# tester.net
KiCad netlist of a schematic drawn in EAGLE
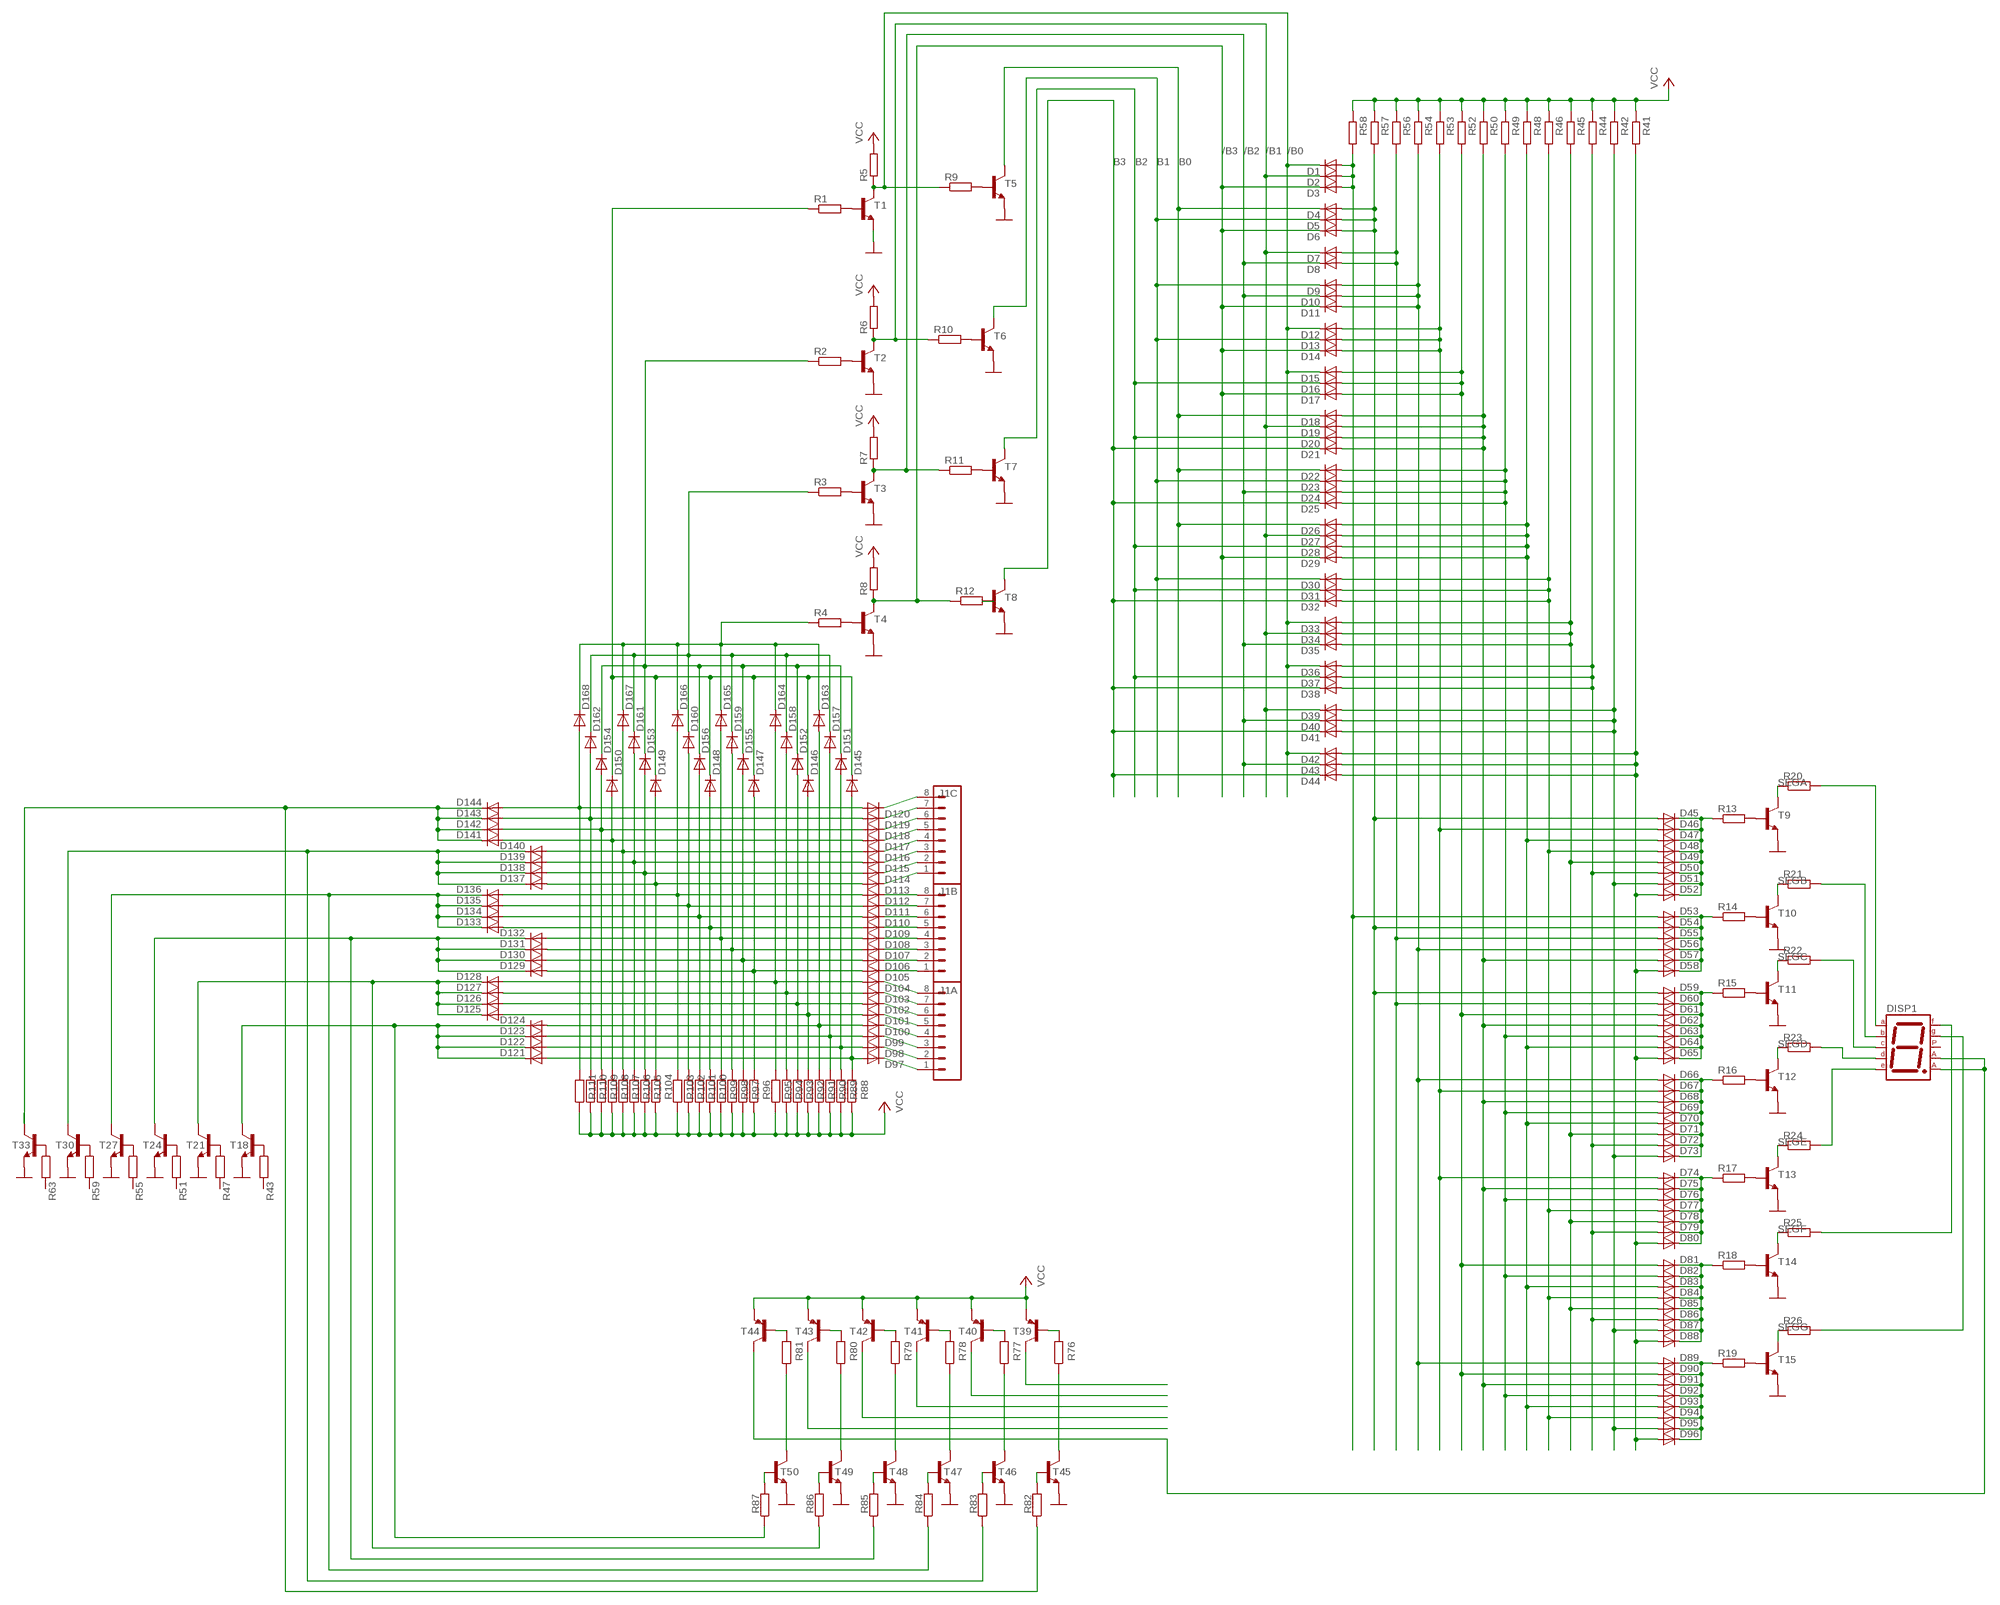
[diagram p0: schematic, sheet 1]

(export (version "E")
  (design (tool "Eeschema 10.0.6"))
  (components
    (comp (ref "D1")
      (value "SMALL_DIODEDO35-7")
      (footprint "eagle-import:DO35-7")
      (libsource (lib "eagle-import") (part "SMALL_DIODEDO35-7"))
    )
    (comp (ref "D2")
      (value "SMALL_DIODEDO35-7")
      (footprint "eagle-import:DO35-7")
      (libsource (lib "eagle-import") (part "SMALL_DIODEDO35-7"))
    )
    (comp (ref "D3")
      (value "SMALL_DIODEDO35-7")
      (footprint "eagle-import:DO35-7")
      (libsource (lib "eagle-import") (part "SMALL_DIODEDO35-7"))
    )
    (comp (ref "D4")
      (value "SMALL_DIODEDO35-7")
      (footprint "eagle-import:DO35-7")
      (libsource (lib "eagle-import") (part "SMALL_DIODEDO35-7"))
    )
    (comp (ref "D5")
      (value "SMALL_DIODEDO35-7")
      (footprint "eagle-import:DO35-7")
      (libsource (lib "eagle-import") (part "SMALL_DIODEDO35-7"))
    )
    (comp (ref "D6")
      (value "SMALL_DIODEDO35-7")
      (footprint "eagle-import:DO35-7")
      (libsource (lib "eagle-import") (part "SMALL_DIODEDO35-7"))
    )
    (comp (ref "D7")
      (value "SMALL_DIODEDO35-7")
      (footprint "eagle-import:DO35-7")
      (libsource (lib "eagle-import") (part "SMALL_DIODEDO35-7"))
    )
    (comp (ref "D8")
      (value "SMALL_DIODEDO35-7")
      (footprint "eagle-import:DO35-7")
      (libsource (lib "eagle-import") (part "SMALL_DIODEDO35-7"))
    )
    (comp (ref "D9")
      (value "SMALL_DIODEDO35-7")
      (footprint "eagle-import:DO35-7")
      (libsource (lib "eagle-import") (part "SMALL_DIODEDO35-7"))
    )
    (comp (ref "D10")
      (value "SMALL_DIODEDO35-7")
      (footprint "eagle-import:DO35-7")
      (libsource (lib "eagle-import") (part "SMALL_DIODEDO35-7"))
    )
    (comp (ref "D11")
      (value "SMALL_DIODEDO35-7")
      (footprint "eagle-import:DO35-7")
      (libsource (lib "eagle-import") (part "SMALL_DIODEDO35-7"))
    )
    (comp (ref "D12")
      (value "SMALL_DIODEDO35-7")
      (footprint "eagle-import:DO35-7")
      (libsource (lib "eagle-import") (part "SMALL_DIODEDO35-7"))
    )
    (comp (ref "D13")
      (value "SMALL_DIODEDO35-7")
      (footprint "eagle-import:DO35-7")
      (libsource (lib "eagle-import") (part "SMALL_DIODEDO35-7"))
    )
    (comp (ref "D14")
      (value "SMALL_DIODEDO35-7")
      (footprint "eagle-import:DO35-7")
      (libsource (lib "eagle-import") (part "SMALL_DIODEDO35-7"))
    )
    (comp (ref "D15")
      (value "SMALL_DIODEDO35-7")
      (footprint "eagle-import:DO35-7")
      (libsource (lib "eagle-import") (part "SMALL_DIODEDO35-7"))
    )
    (comp (ref "D16")
      (value "SMALL_DIODEDO35-7")
      (footprint "eagle-import:DO35-7")
      (libsource (lib "eagle-import") (part "SMALL_DIODEDO35-7"))
    )
    (comp (ref "D17")
      (value "SMALL_DIODEDO35-7")
      (footprint "eagle-import:DO35-7")
      (libsource (lib "eagle-import") (part "SMALL_DIODEDO35-7"))
    )
    (comp (ref "D18")
      (value "SMALL_DIODEDO35-7")
      (footprint "eagle-import:DO35-7")
      (libsource (lib "eagle-import") (part "SMALL_DIODEDO35-7"))
    )
    (comp (ref "D19")
      (value "SMALL_DIODEDO35-7")
      (footprint "eagle-import:DO35-7")
      (libsource (lib "eagle-import") (part "SMALL_DIODEDO35-7"))
    )
    (comp (ref "D20")
      (value "SMALL_DIODEDO35-7")
      (footprint "eagle-import:DO35-7")
      (libsource (lib "eagle-import") (part "SMALL_DIODEDO35-7"))
    )
    (comp (ref "D21")
      (value "SMALL_DIODEDO35-7")
      (footprint "eagle-import:DO35-7")
      (libsource (lib "eagle-import") (part "SMALL_DIODEDO35-7"))
    )
    (comp (ref "D22")
      (value "SMALL_DIODEDO35-7")
      (footprint "eagle-import:DO35-7")
      (libsource (lib "eagle-import") (part "SMALL_DIODEDO35-7"))
    )
    (comp (ref "D23")
      (value "SMALL_DIODEDO35-7")
      (footprint "eagle-import:DO35-7")
      (libsource (lib "eagle-import") (part "SMALL_DIODEDO35-7"))
    )
    (comp (ref "D24")
      (value "SMALL_DIODEDO35-7")
      (footprint "eagle-import:DO35-7")
      (libsource (lib "eagle-import") (part "SMALL_DIODEDO35-7"))
    )
    (comp (ref "D25")
      (value "SMALL_DIODEDO35-7")
      (footprint "eagle-import:DO35-7")
      (libsource (lib "eagle-import") (part "SMALL_DIODEDO35-7"))
    )
    (comp (ref "D26")
      (value "SMALL_DIODEDO35-7")
      (footprint "eagle-import:DO35-7")
      (libsource (lib "eagle-import") (part "SMALL_DIODEDO35-7"))
    )
    (comp (ref "D27")
      (value "SMALL_DIODEDO35-7")
      (footprint "eagle-import:DO35-7")
      (libsource (lib "eagle-import") (part "SMALL_DIODEDO35-7"))
    )
    (comp (ref "D28")
      (value "SMALL_DIODEDO35-7")
      (footprint "eagle-import:DO35-7")
      (libsource (lib "eagle-import") (part "SMALL_DIODEDO35-7"))
    )
    (comp (ref "D29")
      (value "SMALL_DIODEDO35-7")
      (footprint "eagle-import:DO35-7")
      (libsource (lib "eagle-import") (part "SMALL_DIODEDO35-7"))
    )
    (comp (ref "D30")
      (value "SMALL_DIODEDO35-7")
      (footprint "eagle-import:DO35-7")
      (libsource (lib "eagle-import") (part "SMALL_DIODEDO35-7"))
    )
    (comp (ref "D31")
      (value "SMALL_DIODEDO35-7")
      (footprint "eagle-import:DO35-7")
      (libsource (lib "eagle-import") (part "SMALL_DIODEDO35-7"))
    )
    (comp (ref "D32")
      (value "SMALL_DIODEDO35-7")
      (footprint "eagle-import:DO35-7")
      (libsource (lib "eagle-import") (part "SMALL_DIODEDO35-7"))
    )
    (comp (ref "D33")
      (value "SMALL_DIODEDO35-7")
      (footprint "eagle-import:DO35-7")
      (libsource (lib "eagle-import") (part "SMALL_DIODEDO35-7"))
    )
    (comp (ref "D34")
      (value "SMALL_DIODEDO35-7")
      (footprint "eagle-import:DO35-7")
      (libsource (lib "eagle-import") (part "SMALL_DIODEDO35-7"))
    )
    (comp (ref "D35")
      (value "SMALL_DIODEDO35-7")
      (footprint "eagle-import:DO35-7")
      (libsource (lib "eagle-import") (part "SMALL_DIODEDO35-7"))
    )
    (comp (ref "D36")
      (value "SMALL_DIODEDO35-7")
      (footprint "eagle-import:DO35-7")
      (libsource (lib "eagle-import") (part "SMALL_DIODEDO35-7"))
    )
    (comp (ref "D37")
      (value "SMALL_DIODEDO35-7")
      (footprint "eagle-import:DO35-7")
      (libsource (lib "eagle-import") (part "SMALL_DIODEDO35-7"))
    )
    (comp (ref "D38")
      (value "SMALL_DIODEDO35-7")
      (footprint "eagle-import:DO35-7")
      (libsource (lib "eagle-import") (part "SMALL_DIODEDO35-7"))
    )
    (comp (ref "D39")
      (value "SMALL_DIODEDO35-7")
      (footprint "eagle-import:DO35-7")
      (libsource (lib "eagle-import") (part "SMALL_DIODEDO35-7"))
    )
    (comp (ref "D40")
      (value "SMALL_DIODEDO35-7")
      (footprint "eagle-import:DO35-7")
      (libsource (lib "eagle-import") (part "SMALL_DIODEDO35-7"))
    )
    (comp (ref "D41")
      (value "SMALL_DIODEDO35-7")
      (footprint "eagle-import:DO35-7")
      (libsource (lib "eagle-import") (part "SMALL_DIODEDO35-7"))
    )
    (comp (ref "D42")
      (value "SMALL_DIODEDO35-7")
      (footprint "eagle-import:DO35-7")
      (libsource (lib "eagle-import") (part "SMALL_DIODEDO35-7"))
    )
    (comp (ref "D43")
      (value "SMALL_DIODEDO35-7")
      (footprint "eagle-import:DO35-7")
      (libsource (lib "eagle-import") (part "SMALL_DIODEDO35-7"))
    )
    (comp (ref "D44")
      (value "SMALL_DIODEDO35-7")
      (footprint "eagle-import:DO35-7")
      (libsource (lib "eagle-import") (part "SMALL_DIODEDO35-7"))
    )
    (comp (ref "D45")
      (value "SMALL_DIODEDO35-7")
      (footprint "eagle-import:DO35-7")
      (libsource (lib "eagle-import") (part "SMALL_DIODEDO35-7"))
    )
    (comp (ref "D46")
      (value "SMALL_DIODEDO35-7")
      (footprint "eagle-import:DO35-7")
      (libsource (lib "eagle-import") (part "SMALL_DIODEDO35-7"))
    )
    (comp (ref "D47")
      (value "SMALL_DIODEDO35-7")
      (footprint "eagle-import:DO35-7")
      (libsource (lib "eagle-import") (part "SMALL_DIODEDO35-7"))
    )
    (comp (ref "D48")
      (value "SMALL_DIODEDO35-7")
      (footprint "eagle-import:DO35-7")
      (libsource (lib "eagle-import") (part "SMALL_DIODEDO35-7"))
    )
    (comp (ref "D49")
      (value "SMALL_DIODEDO35-7")
      (footprint "eagle-import:DO35-7")
      (libsource (lib "eagle-import") (part "SMALL_DIODEDO35-7"))
    )
    (comp (ref "D50")
      (value "SMALL_DIODEDO35-7")
      (footprint "eagle-import:DO35-7")
      (libsource (lib "eagle-import") (part "SMALL_DIODEDO35-7"))
    )
    (comp (ref "D51")
      (value "SMALL_DIODEDO35-7")
      (footprint "eagle-import:DO35-7")
      (libsource (lib "eagle-import") (part "SMALL_DIODEDO35-7"))
    )
    (comp (ref "D52")
      (value "SMALL_DIODEDO35-7")
      (footprint "eagle-import:DO35-7")
      (libsource (lib "eagle-import") (part "SMALL_DIODEDO35-7"))
    )
    (comp (ref "D53")
      (value "SMALL_DIODEDO35-7")
      (footprint "eagle-import:DO35-7")
      (libsource (lib "eagle-import") (part "SMALL_DIODEDO35-7"))
    )
    (comp (ref "D54")
      (value "SMALL_DIODEDO35-7")
      (footprint "eagle-import:DO35-7")
      (libsource (lib "eagle-import") (part "SMALL_DIODEDO35-7"))
    )
    (comp (ref "D55")
      (value "SMALL_DIODEDO35-7")
      (footprint "eagle-import:DO35-7")
      (libsource (lib "eagle-import") (part "SMALL_DIODEDO35-7"))
    )
    (comp (ref "D56")
      (value "SMALL_DIODEDO35-7")
      (footprint "eagle-import:DO35-7")
      (libsource (lib "eagle-import") (part "SMALL_DIODEDO35-7"))
    )
    (comp (ref "D57")
      (value "SMALL_DIODEDO35-7")
      (footprint "eagle-import:DO35-7")
      (libsource (lib "eagle-import") (part "SMALL_DIODEDO35-7"))
    )
    (comp (ref "D58")
      (value "SMALL_DIODEDO35-7")
      (footprint "eagle-import:DO35-7")
      (libsource (lib "eagle-import") (part "SMALL_DIODEDO35-7"))
    )
    (comp (ref "D59")
      (value "SMALL_DIODEDO35-7")
      (footprint "eagle-import:DO35-7")
      (libsource (lib "eagle-import") (part "SMALL_DIODEDO35-7"))
    )
    (comp (ref "D60")
      (value "SMALL_DIODEDO35-7")
      (footprint "eagle-import:DO35-7")
      (libsource (lib "eagle-import") (part "SMALL_DIODEDO35-7"))
    )
    (comp (ref "D61")
      (value "SMALL_DIODEDO35-7")
      (footprint "eagle-import:DO35-7")
      (libsource (lib "eagle-import") (part "SMALL_DIODEDO35-7"))
    )
    (comp (ref "D62")
      (value "SMALL_DIODEDO35-7")
      (footprint "eagle-import:DO35-7")
      (libsource (lib "eagle-import") (part "SMALL_DIODEDO35-7"))
    )
    (comp (ref "D63")
      (value "SMALL_DIODEDO35-7")
      (footprint "eagle-import:DO35-7")
      (libsource (lib "eagle-import") (part "SMALL_DIODEDO35-7"))
    )
    (comp (ref "D64")
      (value "SMALL_DIODEDO35-7")
      (footprint "eagle-import:DO35-7")
      (libsource (lib "eagle-import") (part "SMALL_DIODEDO35-7"))
    )
    (comp (ref "D65")
      (value "SMALL_DIODEDO35-7")
      (footprint "eagle-import:DO35-7")
      (libsource (lib "eagle-import") (part "SMALL_DIODEDO35-7"))
    )
    (comp (ref "D66")
      (value "SMALL_DIODEDO35-7")
      (footprint "eagle-import:DO35-7")
      (libsource (lib "eagle-import") (part "SMALL_DIODEDO35-7"))
    )
    (comp (ref "D67")
      (value "SMALL_DIODEDO35-7")
      (footprint "eagle-import:DO35-7")
      (libsource (lib "eagle-import") (part "SMALL_DIODEDO35-7"))
    )
    (comp (ref "D68")
      (value "SMALL_DIODEDO35-7")
      (footprint "eagle-import:DO35-7")
      (libsource (lib "eagle-import") (part "SMALL_DIODEDO35-7"))
    )
    (comp (ref "D69")
      (value "SMALL_DIODEDO35-7")
      (footprint "eagle-import:DO35-7")
      (libsource (lib "eagle-import") (part "SMALL_DIODEDO35-7"))
    )
    (comp (ref "D70")
      (value "SMALL_DIODEDO35-7")
      (footprint "eagle-import:DO35-7")
      (libsource (lib "eagle-import") (part "SMALL_DIODEDO35-7"))
    )
    (comp (ref "D71")
      (value "SMALL_DIODEDO35-7")
      (footprint "eagle-import:DO35-7")
      (libsource (lib "eagle-import") (part "SMALL_DIODEDO35-7"))
    )
    (comp (ref "D72")
      (value "SMALL_DIODEDO35-7")
      (footprint "eagle-import:DO35-7")
      (libsource (lib "eagle-import") (part "SMALL_DIODEDO35-7"))
    )
    (comp (ref "D73")
      (value "SMALL_DIODEDO35-7")
      (footprint "eagle-import:DO35-7")
      (libsource (lib "eagle-import") (part "SMALL_DIODEDO35-7"))
    )
    (comp (ref "D74")
      (value "SMALL_DIODEDO35-7")
      (footprint "eagle-import:DO35-7")
      (libsource (lib "eagle-import") (part "SMALL_DIODEDO35-7"))
    )
    (comp (ref "D75")
      (value "SMALL_DIODEDO35-7")
      (footprint "eagle-import:DO35-7")
      (libsource (lib "eagle-import") (part "SMALL_DIODEDO35-7"))
    )
    (comp (ref "D76")
      (value "SMALL_DIODEDO35-7")
      (footprint "eagle-import:DO35-7")
      (libsource (lib "eagle-import") (part "SMALL_DIODEDO35-7"))
    )
    (comp (ref "D77")
      (value "SMALL_DIODEDO35-7")
      (footprint "eagle-import:DO35-7")
      (libsource (lib "eagle-import") (part "SMALL_DIODEDO35-7"))
    )
    (comp (ref "D78")
      (value "SMALL_DIODEDO35-7")
      (footprint "eagle-import:DO35-7")
      (libsource (lib "eagle-import") (part "SMALL_DIODEDO35-7"))
    )
    (comp (ref "D79")
      (value "SMALL_DIODEDO35-7")
      (footprint "eagle-import:DO35-7")
      (libsource (lib "eagle-import") (part "SMALL_DIODEDO35-7"))
    )
    (comp (ref "D80")
      (value "SMALL_DIODEDO35-7")
      (footprint "eagle-import:DO35-7")
      (libsource (lib "eagle-import") (part "SMALL_DIODEDO35-7"))
    )
    (comp (ref "D81")
      (value "SMALL_DIODEDO35-7")
      (footprint "eagle-import:DO35-7")
      (libsource (lib "eagle-import") (part "SMALL_DIODEDO35-7"))
    )
    (comp (ref "D82")
      (value "SMALL_DIODEDO35-7")
      (footprint "eagle-import:DO35-7")
      (libsource (lib "eagle-import") (part "SMALL_DIODEDO35-7"))
    )
    (comp (ref "D83")
      (value "SMALL_DIODEDO35-7")
      (footprint "eagle-import:DO35-7")
      (libsource (lib "eagle-import") (part "SMALL_DIODEDO35-7"))
    )
    (comp (ref "D84")
      (value "SMALL_DIODEDO35-7")
      (footprint "eagle-import:DO35-7")
      (libsource (lib "eagle-import") (part "SMALL_DIODEDO35-7"))
    )
    (comp (ref "D85")
      (value "SMALL_DIODEDO35-7")
      (footprint "eagle-import:DO35-7")
      (libsource (lib "eagle-import") (part "SMALL_DIODEDO35-7"))
    )
    (comp (ref "D86")
      (value "SMALL_DIODEDO35-7")
      (footprint "eagle-import:DO35-7")
      (libsource (lib "eagle-import") (part "SMALL_DIODEDO35-7"))
    )
    (comp (ref "D87")
      (value "SMALL_DIODEDO35-7")
      (footprint "eagle-import:DO35-7")
      (libsource (lib "eagle-import") (part "SMALL_DIODEDO35-7"))
    )
    (comp (ref "D88")
      (value "SMALL_DIODEDO35-7")
      (footprint "eagle-import:DO35-7")
      (libsource (lib "eagle-import") (part "SMALL_DIODEDO35-7"))
    )
    (comp (ref "D89")
      (value "SMALL_DIODEDO35-7")
      (footprint "eagle-import:DO35-7")
      (libsource (lib "eagle-import") (part "SMALL_DIODEDO35-7"))
    )
    (comp (ref "D90")
      (value "SMALL_DIODEDO35-7")
      (footprint "eagle-import:DO35-7")
      (libsource (lib "eagle-import") (part "SMALL_DIODEDO35-7"))
    )
    (comp (ref "D91")
      (value "SMALL_DIODEDO35-7")
      (footprint "eagle-import:DO35-7")
      (libsource (lib "eagle-import") (part "SMALL_DIODEDO35-7"))
    )
    (comp (ref "D92")
      (value "SMALL_DIODEDO35-7")
      (footprint "eagle-import:DO35-7")
      (libsource (lib "eagle-import") (part "SMALL_DIODEDO35-7"))
    )
    (comp (ref "D93")
      (value "SMALL_DIODEDO35-7")
      (footprint "eagle-import:DO35-7")
      (libsource (lib "eagle-import") (part "SMALL_DIODEDO35-7"))
    )
    (comp (ref "D94")
      (value "SMALL_DIODEDO35-7")
      (footprint "eagle-import:DO35-7")
      (libsource (lib "eagle-import") (part "SMALL_DIODEDO35-7"))
    )
    (comp (ref "D95")
      (value "SMALL_DIODEDO35-7")
      (footprint "eagle-import:DO35-7")
      (libsource (lib "eagle-import") (part "SMALL_DIODEDO35-7"))
    )
    (comp (ref "D96")
      (value "SMALL_DIODEDO35-7")
      (footprint "eagle-import:DO35-7")
      (libsource (lib "eagle-import") (part "SMALL_DIODEDO35-7"))
    )
    (comp (ref "D97")
      (value "SMALL_DIODEDO35-7")
      (footprint "eagle-import:DO35-7")
      (libsource (lib "eagle-import") (part "SMALL_DIODEDO35-7"))
    )
    (comp (ref "D98")
      (value "SMALL_DIODEDO35-7")
      (footprint "eagle-import:DO35-7")
      (libsource (lib "eagle-import") (part "SMALL_DIODEDO35-7"))
    )
    (comp (ref "D99")
      (value "SMALL_DIODEDO35-7")
      (footprint "eagle-import:DO35-7")
      (libsource (lib "eagle-import") (part "SMALL_DIODEDO35-7"))
    )
    (comp (ref "D100")
      (value "SMALL_DIODEDO35-7")
      (footprint "eagle-import:DO35-7")
      (libsource (lib "eagle-import") (part "SMALL_DIODEDO35-7"))
    )
    (comp (ref "D101")
      (value "SMALL_DIODEDO35-7")
      (footprint "eagle-import:DO35-7")
      (libsource (lib "eagle-import") (part "SMALL_DIODEDO35-7"))
    )
    (comp (ref "D102")
      (value "SMALL_DIODEDO35-7")
      (footprint "eagle-import:DO35-7")
      (libsource (lib "eagle-import") (part "SMALL_DIODEDO35-7"))
    )
    (comp (ref "D103")
      (value "SMALL_DIODEDO35-7")
      (footprint "eagle-import:DO35-7")
      (libsource (lib "eagle-import") (part "SMALL_DIODEDO35-7"))
    )
    (comp (ref "D104")
      (value "SMALL_DIODEDO35-7")
      (footprint "eagle-import:DO35-7")
      (libsource (lib "eagle-import") (part "SMALL_DIODEDO35-7"))
    )
    (comp (ref "D105")
      (value "SMALL_DIODEDO35-7")
      (footprint "eagle-import:DO35-7")
      (libsource (lib "eagle-import") (part "SMALL_DIODEDO35-7"))
    )
    (comp (ref "D106")
      (value "SMALL_DIODEDO35-7")
      (footprint "eagle-import:DO35-7")
      (libsource (lib "eagle-import") (part "SMALL_DIODEDO35-7"))
    )
    (comp (ref "D107")
      (value "SMALL_DIODEDO35-7")
      (footprint "eagle-import:DO35-7")
      (libsource (lib "eagle-import") (part "SMALL_DIODEDO35-7"))
    )
    (comp (ref "D108")
      (value "SMALL_DIODEDO35-7")
      (footprint "eagle-import:DO35-7")
      (libsource (lib "eagle-import") (part "SMALL_DIODEDO35-7"))
    )
    (comp (ref "D109")
      (value "SMALL_DIODEDO35-7")
      (footprint "eagle-import:DO35-7")
      (libsource (lib "eagle-import") (part "SMALL_DIODEDO35-7"))
    )
    (comp (ref "D110")
      (value "SMALL_DIODEDO35-7")
      (footprint "eagle-import:DO35-7")
      (libsource (lib "eagle-import") (part "SMALL_DIODEDO35-7"))
    )
    (comp (ref "D111")
      (value "SMALL_DIODEDO35-7")
      (footprint "eagle-import:DO35-7")
      (libsource (lib "eagle-import") (part "SMALL_DIODEDO35-7"))
    )
    (comp (ref "D112")
      (value "SMALL_DIODEDO35-7")
      (footprint "eagle-import:DO35-7")
      (libsource (lib "eagle-import") (part "SMALL_DIODEDO35-7"))
    )
    (comp (ref "D113")
      (value "SMALL_DIODEDO35-7")
      (footprint "eagle-import:DO35-7")
      (libsource (lib "eagle-import") (part "SMALL_DIODEDO35-7"))
    )
    (comp (ref "D114")
      (value "SMALL_DIODEDO35-7")
      (footprint "eagle-import:DO35-7")
      (libsource (lib "eagle-import") (part "SMALL_DIODEDO35-7"))
    )
    (comp (ref "D115")
      (value "SMALL_DIODEDO35-7")
      (footprint "eagle-import:DO35-7")
      (libsource (lib "eagle-import") (part "SMALL_DIODEDO35-7"))
    )
    (comp (ref "D116")
      (value "SMALL_DIODEDO35-7")
      (footprint "eagle-import:DO35-7")
      (libsource (lib "eagle-import") (part "SMALL_DIODEDO35-7"))
    )
    (comp (ref "D117")
      (value "SMALL_DIODEDO35-7")
      (footprint "eagle-import:DO35-7")
      (libsource (lib "eagle-import") (part "SMALL_DIODEDO35-7"))
    )
    (comp (ref "D118")
      (value "SMALL_DIODEDO35-7")
      (footprint "eagle-import:DO35-7")
      (libsource (lib "eagle-import") (part "SMALL_DIODEDO35-7"))
    )
    (comp (ref "D119")
      (value "SMALL_DIODEDO35-7")
      (footprint "eagle-import:DO35-7")
      (libsource (lib "eagle-import") (part "SMALL_DIODEDO35-7"))
    )
    (comp (ref "D120")
      (value "SMALL_DIODEDO35-7")
      (footprint "eagle-import:DO35-7")
      (libsource (lib "eagle-import") (part "SMALL_DIODEDO35-7"))
    )
    (comp (ref "D121")
      (value "SMALL_DIODEDO35-7")
      (footprint "eagle-import:DO35-7")
      (libsource (lib "eagle-import") (part "SMALL_DIODEDO35-7"))
    )
    (comp (ref "D122")
      (value "SMALL_DIODEDO35-7")
      (footprint "eagle-import:DO35-7")
      (libsource (lib "eagle-import") (part "SMALL_DIODEDO35-7"))
    )
    (comp (ref "D123")
      (value "SMALL_DIODEDO35-7")
      (footprint "eagle-import:DO35-7")
      (libsource (lib "eagle-import") (part "SMALL_DIODEDO35-7"))
    )
    (comp (ref "D124")
      (value "SMALL_DIODEDO35-7")
      (footprint "eagle-import:DO35-7")
      (libsource (lib "eagle-import") (part "SMALL_DIODEDO35-7"))
    )
    (comp (ref "D125")
      (value "SMALL_DIODEDO35-7")
      (footprint "eagle-import:DO35-7")
      (libsource (lib "eagle-import") (part "SMALL_DIODEDO35-7"))
    )
    (comp (ref "D126")
      (value "SMALL_DIODEDO35-7")
      (footprint "eagle-import:DO35-7")
      (libsource (lib "eagle-import") (part "SMALL_DIODEDO35-7"))
    )
    (comp (ref "D127")
      (value "SMALL_DIODEDO35-7")
      (footprint "eagle-import:DO35-7")
      (libsource (lib "eagle-import") (part "SMALL_DIODEDO35-7"))
    )
    (comp (ref "D128")
      (value "SMALL_DIODEDO35-7")
      (footprint "eagle-import:DO35-7")
      (libsource (lib "eagle-import") (part "SMALL_DIODEDO35-7"))
    )
    (comp (ref "D129")
      (value "SMALL_DIODEDO35-7")
      (footprint "eagle-import:DO35-7")
      (libsource (lib "eagle-import") (part "SMALL_DIODEDO35-7"))
    )
    (comp (ref "D130")
      (value "SMALL_DIODEDO35-7")
      (footprint "eagle-import:DO35-7")
      (libsource (lib "eagle-import") (part "SMALL_DIODEDO35-7"))
    )
    (comp (ref "D131")
      (value "SMALL_DIODEDO35-7")
      (footprint "eagle-import:DO35-7")
      (libsource (lib "eagle-import") (part "SMALL_DIODEDO35-7"))
    )
    (comp (ref "D132")
      (value "SMALL_DIODEDO35-7")
      (footprint "eagle-import:DO35-7")
      (libsource (lib "eagle-import") (part "SMALL_DIODEDO35-7"))
    )
    (comp (ref "D133")
      (value "SMALL_DIODEDO35-7")
      (footprint "eagle-import:DO35-7")
      (libsource (lib "eagle-import") (part "SMALL_DIODEDO35-7"))
    )
    (comp (ref "D134")
      (value "SMALL_DIODEDO35-7")
      (footprint "eagle-import:DO35-7")
      (libsource (lib "eagle-import") (part "SMALL_DIODEDO35-7"))
    )
    (comp (ref "D135")
      (value "SMALL_DIODEDO35-7")
      (footprint "eagle-import:DO35-7")
      (libsource (lib "eagle-import") (part "SMALL_DIODEDO35-7"))
    )
    (comp (ref "D136")
      (value "SMALL_DIODEDO35-7")
      (footprint "eagle-import:DO35-7")
      (libsource (lib "eagle-import") (part "SMALL_DIODEDO35-7"))
    )
    (comp (ref "D137")
      (value "SMALL_DIODEDO35-7")
      (footprint "eagle-import:DO35-7")
      (libsource (lib "eagle-import") (part "SMALL_DIODEDO35-7"))
    )
    (comp (ref "D138")
      (value "SMALL_DIODEDO35-7")
      (footprint "eagle-import:DO35-7")
      (libsource (lib "eagle-import") (part "SMALL_DIODEDO35-7"))
    )
    (comp (ref "D139")
      (value "SMALL_DIODEDO35-7")
      (footprint "eagle-import:DO35-7")
      (libsource (lib "eagle-import") (part "SMALL_DIODEDO35-7"))
    )
    (comp (ref "D140")
      (value "SMALL_DIODEDO35-7")
      (footprint "eagle-import:DO35-7")
      (libsource (lib "eagle-import") (part "SMALL_DIODEDO35-7"))
    )
    (comp (ref "D141")
      (value "SMALL_DIODEDO35-7")
      (footprint "eagle-import:DO35-7")
      (libsource (lib "eagle-import") (part "SMALL_DIODEDO35-7"))
    )
    (comp (ref "D142")
      (value "SMALL_DIODEDO35-7")
      (footprint "eagle-import:DO35-7")
      (libsource (lib "eagle-import") (part "SMALL_DIODEDO35-7"))
    )
    (comp (ref "D143")
      (value "SMALL_DIODEDO35-7")
      (footprint "eagle-import:DO35-7")
      (libsource (lib "eagle-import") (part "SMALL_DIODEDO35-7"))
    )
    (comp (ref "D144")
      (value "SMALL_DIODEDO35-7")
      (footprint "eagle-import:DO35-7")
      (libsource (lib "eagle-import") (part "SMALL_DIODEDO35-7"))
    )
    (comp (ref "D145")
      (value "SMALL_DIODEDO35-7")
      (footprint "eagle-import:DO35-7")
      (libsource (lib "eagle-import") (part "SMALL_DIODEDO35-7"))
    )
    (comp (ref "D146")
      (value "SMALL_DIODEDO35-7")
      (footprint "eagle-import:DO35-7")
      (libsource (lib "eagle-import") (part "SMALL_DIODEDO35-7"))
    )
    (comp (ref "D147")
      (value "SMALL_DIODEDO35-7")
      (footprint "eagle-import:DO35-7")
      (libsource (lib "eagle-import") (part "SMALL_DIODEDO35-7"))
    )
    (comp (ref "D148")
      (value "SMALL_DIODEDO35-7")
      (footprint "eagle-import:DO35-7")
      (libsource (lib "eagle-import") (part "SMALL_DIODEDO35-7"))
    )
    (comp (ref "D149")
      (value "SMALL_DIODEDO35-7")
      (footprint "eagle-import:DO35-7")
      (libsource (lib "eagle-import") (part "SMALL_DIODEDO35-7"))
    )
    (comp (ref "D150")
      (value "SMALL_DIODEDO35-7")
      (footprint "eagle-import:DO35-7")
      (libsource (lib "eagle-import") (part "SMALL_DIODEDO35-7"))
    )
    (comp (ref "D151")
      (value "SMALL_DIODEDO35-7")
      (footprint "eagle-import:DO35-7")
      (libsource (lib "eagle-import") (part "SMALL_DIODEDO35-7"))
    )
    (comp (ref "D152")
      (value "SMALL_DIODEDO35-7")
      (footprint "eagle-import:DO35-7")
      (libsource (lib "eagle-import") (part "SMALL_DIODEDO35-7"))
    )
    (comp (ref "D153")
      (value "SMALL_DIODEDO35-7")
      (footprint "eagle-import:DO35-7")
      (libsource (lib "eagle-import") (part "SMALL_DIODEDO35-7"))
    )
    (comp (ref "D154")
      (value "SMALL_DIODEDO35-7")
      (footprint "eagle-import:DO35-7")
      (libsource (lib "eagle-import") (part "SMALL_DIODEDO35-7"))
    )
    (comp (ref "D155")
      (value "SMALL_DIODEDO35-7")
      (footprint "eagle-import:DO35-7")
      (libsource (lib "eagle-import") (part "SMALL_DIODEDO35-7"))
    )
    (comp (ref "D156")
      (value "SMALL_DIODEDO35-7")
      (footprint "eagle-import:DO35-7")
      (libsource (lib "eagle-import") (part "SMALL_DIODEDO35-7"))
    )
    (comp (ref "D157")
      (value "SMALL_DIODEDO35-7")
      (footprint "eagle-import:DO35-7")
      (libsource (lib "eagle-import") (part "SMALL_DIODEDO35-7"))
    )
    (comp (ref "D158")
      (value "SMALL_DIODEDO35-7")
      (footprint "eagle-import:DO35-7")
      (libsource (lib "eagle-import") (part "SMALL_DIODEDO35-7"))
    )
    (comp (ref "D159")
      (value "SMALL_DIODEDO35-7")
      (footprint "eagle-import:DO35-7")
      (libsource (lib "eagle-import") (part "SMALL_DIODEDO35-7"))
    )
    (comp (ref "D160")
      (value "SMALL_DIODEDO35-7")
      (footprint "eagle-import:DO35-7")
      (libsource (lib "eagle-import") (part "SMALL_DIODEDO35-7"))
    )
    (comp (ref "D161")
      (value "SMALL_DIODEDO35-7")
      (footprint "eagle-import:DO35-7")
      (libsource (lib "eagle-import") (part "SMALL_DIODEDO35-7"))
    )
    (comp (ref "D162")
      (value "SMALL_DIODEDO35-7")
      (footprint "eagle-import:DO35-7")
      (libsource (lib "eagle-import") (part "SMALL_DIODEDO35-7"))
    )
    (comp (ref "D163")
      (value "SMALL_DIODEDO35-7")
      (footprint "eagle-import:DO35-7")
      (libsource (lib "eagle-import") (part "SMALL_DIODEDO35-7"))
    )
    (comp (ref "D164")
      (value "SMALL_DIODEDO35-7")
      (footprint "eagle-import:DO35-7")
      (libsource (lib "eagle-import") (part "SMALL_DIODEDO35-7"))
    )
    (comp (ref "D165")
      (value "SMALL_DIODEDO35-7")
      (footprint "eagle-import:DO35-7")
      (libsource (lib "eagle-import") (part "SMALL_DIODEDO35-7"))
    )
    (comp (ref "D166")
      (value "SMALL_DIODEDO35-7")
      (footprint "eagle-import:DO35-7")
      (libsource (lib "eagle-import") (part "SMALL_DIODEDO35-7"))
    )
    (comp (ref "D167")
      (value "SMALL_DIODEDO35-7")
      (footprint "eagle-import:DO35-7")
      (libsource (lib "eagle-import") (part "SMALL_DIODEDO35-7"))
    )
    (comp (ref "D168")
      (value "SMALL_DIODEDO35-7")
      (footprint "eagle-import:DO35-7")
      (libsource (lib "eagle-import") (part "SMALL_DIODEDO35-7"))
    )
    (comp (ref "DISP1")
      (value "7SEG-CA")
      (footprint "eagle-import:7SEG-13")
      (libsource (lib "eagle-import") (part "7SEG-CA"))
    )
    (comp (ref "J1A")
      (value "CONN_08\"")
      (footprint "eagle-import:1X08")
      (libsource (lib "eagle-import") (part "CONN_08{dblquote}"))
    )
    (comp (ref "J1B")
      (value "CONN_08\"")
      (footprint "eagle-import:1X08")
      (libsource (lib "eagle-import") (part "CONN_08{dblquote}"))
    )
    (comp (ref "J1C")
      (value "CONN_08\"")
      (footprint "eagle-import:1X08")
      (libsource (lib "eagle-import") (part "CONN_08{dblquote}"))
    )
    (comp (ref "R1")
      (value "RESISTOR7MM")
      (footprint "eagle-import:7MM_RESISTOR")
      (libsource (lib "eagle-import") (part "RESISTOR7MM"))
    )
    (comp (ref "R2")
      (value "RESISTOR7MM")
      (footprint "eagle-import:7MM_RESISTOR")
      (libsource (lib "eagle-import") (part "RESISTOR7MM"))
    )
    (comp (ref "R3")
      (value "RESISTOR7MM")
      (footprint "eagle-import:7MM_RESISTOR")
      (libsource (lib "eagle-import") (part "RESISTOR7MM"))
    )
    (comp (ref "R4")
      (value "RESISTOR7MM")
      (footprint "eagle-import:7MM_RESISTOR")
      (libsource (lib "eagle-import") (part "RESISTOR7MM"))
    )
    (comp (ref "R5")
      (value "RESISTOR7MM")
      (footprint "eagle-import:7MM_RESISTOR")
      (libsource (lib "eagle-import") (part "RESISTOR7MM"))
    )
    (comp (ref "R6")
      (value "RESISTOR7MM")
      (footprint "eagle-import:7MM_RESISTOR")
      (libsource (lib "eagle-import") (part "RESISTOR7MM"))
    )
    (comp (ref "R7")
      (value "RESISTOR7MM")
      (footprint "eagle-import:7MM_RESISTOR")
      (libsource (lib "eagle-import") (part "RESISTOR7MM"))
    )
    (comp (ref "R8")
      (value "RESISTOR7MM")
      (footprint "eagle-import:7MM_RESISTOR")
      (libsource (lib "eagle-import") (part "RESISTOR7MM"))
    )
    (comp (ref "R9")
      (value "RESISTOR7MM")
      (footprint "eagle-import:7MM_RESISTOR")
      (libsource (lib "eagle-import") (part "RESISTOR7MM"))
    )
    (comp (ref "R10")
      (value "RESISTOR7MM")
      (footprint "eagle-import:7MM_RESISTOR")
      (libsource (lib "eagle-import") (part "RESISTOR7MM"))
    )
    (comp (ref "R11")
      (value "RESISTOR7MM")
      (footprint "eagle-import:7MM_RESISTOR")
      (libsource (lib "eagle-import") (part "RESISTOR7MM"))
    )
    (comp (ref "R12")
      (value "RESISTOR7MM")
      (footprint "eagle-import:7MM_RESISTOR")
      (libsource (lib "eagle-import") (part "RESISTOR7MM"))
    )
    (comp (ref "R13")
      (value "RESISTOR7MM")
      (footprint "eagle-import:7MM_RESISTOR")
      (libsource (lib "eagle-import") (part "RESISTOR7MM"))
    )
    (comp (ref "R14")
      (value "RESISTOR7MM")
      (footprint "eagle-import:7MM_RESISTOR")
      (libsource (lib "eagle-import") (part "RESISTOR7MM"))
    )
    (comp (ref "R15")
      (value "RESISTOR7MM")
      (footprint "eagle-import:7MM_RESISTOR")
      (libsource (lib "eagle-import") (part "RESISTOR7MM"))
    )
    (comp (ref "R16")
      (value "RESISTOR7MM")
      (footprint "eagle-import:7MM_RESISTOR")
      (libsource (lib "eagle-import") (part "RESISTOR7MM"))
    )
    (comp (ref "R17")
      (value "RESISTOR7MM")
      (footprint "eagle-import:7MM_RESISTOR")
      (libsource (lib "eagle-import") (part "RESISTOR7MM"))
    )
    (comp (ref "R18")
      (value "RESISTOR7MM")
      (footprint "eagle-import:7MM_RESISTOR")
      (libsource (lib "eagle-import") (part "RESISTOR7MM"))
    )
    (comp (ref "R19")
      (value "RESISTOR7MM")
      (footprint "eagle-import:7MM_RESISTOR")
      (libsource (lib "eagle-import") (part "RESISTOR7MM"))
    )
    (comp (ref "R20")
      (value "RESISTOR7MM")
      (footprint "eagle-import:7MM_RESISTOR")
      (libsource (lib "eagle-import") (part "RESISTOR7MM"))
    )
    (comp (ref "R21")
      (value "RESISTOR7MM")
      (footprint "eagle-import:7MM_RESISTOR")
      (libsource (lib "eagle-import") (part "RESISTOR7MM"))
    )
    (comp (ref "R22")
      (value "RESISTOR7MM")
      (footprint "eagle-import:7MM_RESISTOR")
      (libsource (lib "eagle-import") (part "RESISTOR7MM"))
    )
    (comp (ref "R23")
      (value "RESISTOR7MM")
      (footprint "eagle-import:7MM_RESISTOR")
      (libsource (lib "eagle-import") (part "RESISTOR7MM"))
    )
    (comp (ref "R24")
      (value "RESISTOR7MM")
      (footprint "eagle-import:7MM_RESISTOR")
      (libsource (lib "eagle-import") (part "RESISTOR7MM"))
    )
    (comp (ref "R25")
      (value "RESISTOR7MM")
      (footprint "eagle-import:7MM_RESISTOR")
      (libsource (lib "eagle-import") (part "RESISTOR7MM"))
    )
    (comp (ref "R26")
      (value "RESISTOR7MM")
      (footprint "eagle-import:7MM_RESISTOR")
      (libsource (lib "eagle-import") (part "RESISTOR7MM"))
    )
    (comp (ref "R41")
      (value "RESISTOR7MM")
      (footprint "eagle-import:7MM_RESISTOR")
      (libsource (lib "eagle-import") (part "RESISTOR7MM"))
    )
    (comp (ref "R42")
      (value "RESISTOR7MM")
      (footprint "eagle-import:7MM_RESISTOR")
      (libsource (lib "eagle-import") (part "RESISTOR7MM"))
    )
    (comp (ref "R43")
      (value "RESISTOR7MM")
      (footprint "eagle-import:7MM_RESISTOR")
      (libsource (lib "eagle-import") (part "RESISTOR7MM"))
    )
    (comp (ref "R44")
      (value "RESISTOR7MM")
      (footprint "eagle-import:7MM_RESISTOR")
      (libsource (lib "eagle-import") (part "RESISTOR7MM"))
    )
    (comp (ref "R45")
      (value "RESISTOR7MM")
      (footprint "eagle-import:7MM_RESISTOR")
      (libsource (lib "eagle-import") (part "RESISTOR7MM"))
    )
    (comp (ref "R46")
      (value "RESISTOR7MM")
      (footprint "eagle-import:7MM_RESISTOR")
      (libsource (lib "eagle-import") (part "RESISTOR7MM"))
    )
    (comp (ref "R47")
      (value "RESISTOR7MM")
      (footprint "eagle-import:7MM_RESISTOR")
      (libsource (lib "eagle-import") (part "RESISTOR7MM"))
    )
    (comp (ref "R48")
      (value "RESISTOR7MM")
      (footprint "eagle-import:7MM_RESISTOR")
      (libsource (lib "eagle-import") (part "RESISTOR7MM"))
    )
    (comp (ref "R49")
      (value "RESISTOR7MM")
      (footprint "eagle-import:7MM_RESISTOR")
      (libsource (lib "eagle-import") (part "RESISTOR7MM"))
    )
    (comp (ref "R50")
      (value "RESISTOR7MM")
      (footprint "eagle-import:7MM_RESISTOR")
      (libsource (lib "eagle-import") (part "RESISTOR7MM"))
    )
    (comp (ref "R51")
      (value "RESISTOR7MM")
      (footprint "eagle-import:7MM_RESISTOR")
      (libsource (lib "eagle-import") (part "RESISTOR7MM"))
    )
    (comp (ref "R52")
      (value "RESISTOR7MM")
      (footprint "eagle-import:7MM_RESISTOR")
      (libsource (lib "eagle-import") (part "RESISTOR7MM"))
    )
    (comp (ref "R53")
      (value "RESISTOR7MM")
      (footprint "eagle-import:7MM_RESISTOR")
      (libsource (lib "eagle-import") (part "RESISTOR7MM"))
    )
    (comp (ref "R54")
      (value "RESISTOR7MM")
      (footprint "eagle-import:7MM_RESISTOR")
      (libsource (lib "eagle-import") (part "RESISTOR7MM"))
    )
    (comp (ref "R55")
      (value "RESISTOR7MM")
      (footprint "eagle-import:7MM_RESISTOR")
      (libsource (lib "eagle-import") (part "RESISTOR7MM"))
    )
    (comp (ref "R56")
      (value "RESISTOR7MM")
      (footprint "eagle-import:7MM_RESISTOR")
      (libsource (lib "eagle-import") (part "RESISTOR7MM"))
    )
    (comp (ref "R57")
      (value "RESISTOR7MM")
      (footprint "eagle-import:7MM_RESISTOR")
      (libsource (lib "eagle-import") (part "RESISTOR7MM"))
    )
    (comp (ref "R58")
      (value "RESISTOR7MM")
      (footprint "eagle-import:7MM_RESISTOR")
      (libsource (lib "eagle-import") (part "RESISTOR7MM"))
    )
    (comp (ref "R59")
      (value "RESISTOR7MM")
      (footprint "eagle-import:7MM_RESISTOR")
      (libsource (lib "eagle-import") (part "RESISTOR7MM"))
    )
    (comp (ref "R63")
      (value "RESISTOR7MM")
      (footprint "eagle-import:7MM_RESISTOR")
      (libsource (lib "eagle-import") (part "RESISTOR7MM"))
    )
    (comp (ref "R76")
      (value "RESISTOR7MM")
      (footprint "eagle-import:7MM_RESISTOR")
      (libsource (lib "eagle-import") (part "RESISTOR7MM"))
    )
    (comp (ref "R77")
      (value "RESISTOR7MM")
      (footprint "eagle-import:7MM_RESISTOR")
      (libsource (lib "eagle-import") (part "RESISTOR7MM"))
    )
    (comp (ref "R78")
      (value "RESISTOR7MM")
      (footprint "eagle-import:7MM_RESISTOR")
      (libsource (lib "eagle-import") (part "RESISTOR7MM"))
    )
    (comp (ref "R79")
      (value "RESISTOR7MM")
      (footprint "eagle-import:7MM_RESISTOR")
      (libsource (lib "eagle-import") (part "RESISTOR7MM"))
    )
    (comp (ref "R80")
      (value "RESISTOR7MM")
      (footprint "eagle-import:7MM_RESISTOR")
      (libsource (lib "eagle-import") (part "RESISTOR7MM"))
    )
    (comp (ref "R81")
      (value "RESISTOR7MM")
      (footprint "eagle-import:7MM_RESISTOR")
      (libsource (lib "eagle-import") (part "RESISTOR7MM"))
    )
    (comp (ref "R82")
      (value "RESISTOR7MM")
      (footprint "eagle-import:7MM_RESISTOR")
      (libsource (lib "eagle-import") (part "RESISTOR7MM"))
    )
    (comp (ref "R83")
      (value "RESISTOR7MM")
      (footprint "eagle-import:7MM_RESISTOR")
      (libsource (lib "eagle-import") (part "RESISTOR7MM"))
    )
    (comp (ref "R84")
      (value "RESISTOR7MM")
      (footprint "eagle-import:7MM_RESISTOR")
      (libsource (lib "eagle-import") (part "RESISTOR7MM"))
    )
    (comp (ref "R85")
      (value "RESISTOR7MM")
      (footprint "eagle-import:7MM_RESISTOR")
      (libsource (lib "eagle-import") (part "RESISTOR7MM"))
    )
    (comp (ref "R86")
      (value "RESISTOR7MM")
      (footprint "eagle-import:7MM_RESISTOR")
      (libsource (lib "eagle-import") (part "RESISTOR7MM"))
    )
    (comp (ref "R87")
      (value "RESISTOR7MM")
      (footprint "eagle-import:7MM_RESISTOR")
      (libsource (lib "eagle-import") (part "RESISTOR7MM"))
    )
    (comp (ref "R88")
      (value "RESISTOR7MM")
      (footprint "eagle-import:7MM_RESISTOR")
      (libsource (lib "eagle-import") (part "RESISTOR7MM"))
    )
    (comp (ref "R89")
      (value "RESISTOR7MM")
      (footprint "eagle-import:7MM_RESISTOR")
      (libsource (lib "eagle-import") (part "RESISTOR7MM"))
    )
    (comp (ref "R90")
      (value "RESISTOR7MM")
      (footprint "eagle-import:7MM_RESISTOR")
      (libsource (lib "eagle-import") (part "RESISTOR7MM"))
    )
    (comp (ref "R91")
      (value "RESISTOR7MM")
      (footprint "eagle-import:7MM_RESISTOR")
      (libsource (lib "eagle-import") (part "RESISTOR7MM"))
    )
    (comp (ref "R92")
      (value "RESISTOR7MM")
      (footprint "eagle-import:7MM_RESISTOR")
      (libsource (lib "eagle-import") (part "RESISTOR7MM"))
    )
    (comp (ref "R93")
      (value "RESISTOR7MM")
      (footprint "eagle-import:7MM_RESISTOR")
      (libsource (lib "eagle-import") (part "RESISTOR7MM"))
    )
    (comp (ref "R94")
      (value "RESISTOR7MM")
      (footprint "eagle-import:7MM_RESISTOR")
      (libsource (lib "eagle-import") (part "RESISTOR7MM"))
    )
    (comp (ref "R95")
      (value "RESISTOR7MM")
      (footprint "eagle-import:7MM_RESISTOR")
      (libsource (lib "eagle-import") (part "RESISTOR7MM"))
    )
    (comp (ref "R96")
      (value "RESISTOR7MM")
      (footprint "eagle-import:7MM_RESISTOR")
      (libsource (lib "eagle-import") (part "RESISTOR7MM"))
    )
    (comp (ref "R97")
      (value "RESISTOR7MM")
      (footprint "eagle-import:7MM_RESISTOR")
      (libsource (lib "eagle-import") (part "RESISTOR7MM"))
    )
    (comp (ref "R98")
      (value "RESISTOR7MM")
      (footprint "eagle-import:7MM_RESISTOR")
      (libsource (lib "eagle-import") (part "RESISTOR7MM"))
    )
    (comp (ref "R99")
      (value "RESISTOR7MM")
      (footprint "eagle-import:7MM_RESISTOR")
      (libsource (lib "eagle-import") (part "RESISTOR7MM"))
    )
    (comp (ref "R100")
      (value "RESISTOR7MM")
      (footprint "eagle-import:7MM_RESISTOR")
      (libsource (lib "eagle-import") (part "RESISTOR7MM"))
    )
    (comp (ref "R101")
      (value "RESISTOR7MM")
      (footprint "eagle-import:7MM_RESISTOR")
      (libsource (lib "eagle-import") (part "RESISTOR7MM"))
    )
    (comp (ref "R102")
      (value "RESISTOR7MM")
      (footprint "eagle-import:7MM_RESISTOR")
      (libsource (lib "eagle-import") (part "RESISTOR7MM"))
    )
    (comp (ref "R103")
      (value "RESISTOR7MM")
      (footprint "eagle-import:7MM_RESISTOR")
      (libsource (lib "eagle-import") (part "RESISTOR7MM"))
    )
    (comp (ref "R104")
      (value "RESISTOR7MM")
      (footprint "eagle-import:7MM_RESISTOR")
      (libsource (lib "eagle-import") (part "RESISTOR7MM"))
    )
    (comp (ref "R105")
      (value "RESISTOR7MM")
      (footprint "eagle-import:7MM_RESISTOR")
      (libsource (lib "eagle-import") (part "RESISTOR7MM"))
    )
    (comp (ref "R106")
      (value "RESISTOR7MM")
      (footprint "eagle-import:7MM_RESISTOR")
      (libsource (lib "eagle-import") (part "RESISTOR7MM"))
    )
    (comp (ref "R107")
      (value "RESISTOR7MM")
      (footprint "eagle-import:7MM_RESISTOR")
      (libsource (lib "eagle-import") (part "RESISTOR7MM"))
    )
    (comp (ref "R108")
      (value "RESISTOR7MM")
      (footprint "eagle-import:7MM_RESISTOR")
      (libsource (lib "eagle-import") (part "RESISTOR7MM"))
    )
    (comp (ref "R109")
      (value "RESISTOR7MM")
      (footprint "eagle-import:7MM_RESISTOR")
      (libsource (lib "eagle-import") (part "RESISTOR7MM"))
    )
    (comp (ref "R110")
      (value "RESISTOR7MM")
      (footprint "eagle-import:7MM_RESISTOR")
      (libsource (lib "eagle-import") (part "RESISTOR7MM"))
    )
    (comp (ref "R111")
      (value "RESISTOR7MM")
      (footprint "eagle-import:7MM_RESISTOR")
      (libsource (lib "eagle-import") (part "RESISTOR7MM"))
    )
    (comp (ref "T1")
      (value "BC547B-NPN-TO92-CBE")
      (footprint "eagle-import:TO92-CBE")
      (libsource (lib "eagle-import") (part "-NPN-TO92-CBEBC547B"))
    )
    (comp (ref "T2")
      (value "BC547B-NPN-TO92-CBE")
      (footprint "eagle-import:TO92-CBE")
      (libsource (lib "eagle-import") (part "-NPN-TO92-CBEBC547B"))
    )
    (comp (ref "T3")
      (value "BC547B-NPN-TO92-CBE")
      (footprint "eagle-import:TO92-CBE")
      (libsource (lib "eagle-import") (part "-NPN-TO92-CBEBC547B"))
    )
    (comp (ref "T4")
      (value "BC547B-NPN-TO92-CBE")
      (footprint "eagle-import:TO92-CBE")
      (libsource (lib "eagle-import") (part "-NPN-TO92-CBEBC547B"))
    )
    (comp (ref "T5")
      (value "BC547B-NPN-TO92-CBE")
      (footprint "eagle-import:TO92-CBE")
      (libsource (lib "eagle-import") (part "-NPN-TO92-CBEBC547B"))
    )
    (comp (ref "T6")
      (value "BC547B-NPN-TO92-CBE")
      (footprint "eagle-import:TO92-CBE")
      (libsource (lib "eagle-import") (part "-NPN-TO92-CBEBC547B"))
    )
    (comp (ref "T7")
      (value "BC547B-NPN-TO92-CBE")
      (footprint "eagle-import:TO92-CBE")
      (libsource (lib "eagle-import") (part "-NPN-TO92-CBEBC547B"))
    )
    (comp (ref "T8")
      (value "BC547B-NPN-TO92-CBE")
      (footprint "eagle-import:TO92-CBE")
      (libsource (lib "eagle-import") (part "-NPN-TO92-CBEBC547B"))
    )
    (comp (ref "T9")
      (value "BC547B-NPN-TO92-CBE")
      (footprint "eagle-import:TO92-CBE")
      (libsource (lib "eagle-import") (part "-NPN-TO92-CBEBC547B"))
    )
    (comp (ref "T10")
      (value "BC547B-NPN-TO92-CBE")
      (footprint "eagle-import:TO92-CBE")
      (libsource (lib "eagle-import") (part "-NPN-TO92-CBEBC547B"))
    )
    (comp (ref "T11")
      (value "BC547B-NPN-TO92-CBE")
      (footprint "eagle-import:TO92-CBE")
      (libsource (lib "eagle-import") (part "-NPN-TO92-CBEBC547B"))
    )
    (comp (ref "T12")
      (value "BC547B-NPN-TO92-CBE")
      (footprint "eagle-import:TO92-CBE")
      (libsource (lib "eagle-import") (part "-NPN-TO92-CBEBC547B"))
    )
    (comp (ref "T13")
      (value "BC547B-NPN-TO92-CBE")
      (footprint "eagle-import:TO92-CBE")
      (libsource (lib "eagle-import") (part "-NPN-TO92-CBEBC547B"))
    )
    (comp (ref "T14")
      (value "BC547B-NPN-TO92-CBE")
      (footprint "eagle-import:TO92-CBE")
      (libsource (lib "eagle-import") (part "-NPN-TO92-CBEBC547B"))
    )
    (comp (ref "T15")
      (value "BC547B-NPN-TO92-CBE")
      (footprint "eagle-import:TO92-CBE")
      (libsource (lib "eagle-import") (part "-NPN-TO92-CBEBC547B"))
    )
    (comp (ref "T18")
      (value "BC547B-NPN-TO92-CBE")
      (footprint "eagle-import:TO92-CBE")
      (libsource (lib "eagle-import") (part "-NPN-TO92-CBEBC547B"))
    )
    (comp (ref "T21")
      (value "BC547B-NPN-TO92-CBE")
      (footprint "eagle-import:TO92-CBE")
      (libsource (lib "eagle-import") (part "-NPN-TO92-CBEBC547B"))
    )
    (comp (ref "T24")
      (value "BC547B-NPN-TO92-CBE")
      (footprint "eagle-import:TO92-CBE")
      (libsource (lib "eagle-import") (part "-NPN-TO92-CBEBC547B"))
    )
    (comp (ref "T27")
      (value "BC547B-NPN-TO92-CBE")
      (footprint "eagle-import:TO92-CBE")
      (libsource (lib "eagle-import") (part "-NPN-TO92-CBEBC547B"))
    )
    (comp (ref "T30")
      (value "BC547B-NPN-TO92-CBE")
      (footprint "eagle-import:TO92-CBE")
      (libsource (lib "eagle-import") (part "-NPN-TO92-CBEBC547B"))
    )
    (comp (ref "T33")
      (value "BC547B-NPN-TO92-CBE")
      (footprint "eagle-import:TO92-CBE")
      (libsource (lib "eagle-import") (part "-NPN-TO92-CBEBC547B"))
    )
    (comp (ref "T39")
      (value "BC557B-PNP-TO92-EBC")
      (footprint "eagle-import:TO92-EBC")
      (libsource (lib "eagle-import") (part "-PNP-TO92-EBCBC557B"))
    )
    (comp (ref "T40")
      (value "BC557B-PNP-TO92-EBC")
      (footprint "eagle-import:TO92-EBC")
      (libsource (lib "eagle-import") (part "-PNP-TO92-EBCBC557B"))
    )
    (comp (ref "T41")
      (value "BC557B-PNP-TO92-EBC")
      (footprint "eagle-import:TO92-EBC")
      (libsource (lib "eagle-import") (part "-PNP-TO92-EBCBC557B"))
    )
    (comp (ref "T42")
      (value "BC557B-PNP-TO92-EBC")
      (footprint "eagle-import:TO92-EBC")
      (libsource (lib "eagle-import") (part "-PNP-TO92-EBCBC557B"))
    )
    (comp (ref "T43")
      (value "BC557B-PNP-TO92-EBC")
      (footprint "eagle-import:TO92-EBC")
      (libsource (lib "eagle-import") (part "-PNP-TO92-EBCBC557B"))
    )
    (comp (ref "T44")
      (value "BC557B-PNP-TO92-EBC")
      (footprint "eagle-import:TO92-EBC")
      (libsource (lib "eagle-import") (part "-PNP-TO92-EBCBC557B"))
    )
    (comp (ref "T45")
      (value "BC547B-NPN-TO92-CBE")
      (footprint "eagle-import:TO92-CBE")
      (libsource (lib "eagle-import") (part "-NPN-TO92-CBEBC547B"))
    )
    (comp (ref "T46")
      (value "BC547B-NPN-TO92-CBE")
      (footprint "eagle-import:TO92-CBE")
      (libsource (lib "eagle-import") (part "-NPN-TO92-CBEBC547B"))
    )
    (comp (ref "T47")
      (value "BC547B-NPN-TO92-CBE")
      (footprint "eagle-import:TO92-CBE")
      (libsource (lib "eagle-import") (part "-NPN-TO92-CBEBC547B"))
    )
    (comp (ref "T48")
      (value "BC547B-NPN-TO92-CBE")
      (footprint "eagle-import:TO92-CBE")
      (libsource (lib "eagle-import") (part "-NPN-TO92-CBEBC547B"))
    )
    (comp (ref "T49")
      (value "BC547B-NPN-TO92-CBE")
      (footprint "eagle-import:TO92-CBE")
      (libsource (lib "eagle-import") (part "-NPN-TO92-CBEBC547B"))
    )
    (comp (ref "T50")
      (value "BC547B-NPN-TO92-CBE")
      (footprint "eagle-import:TO92-CBE")
      (libsource (lib "eagle-import") (part "-NPN-TO92-CBEBC547B"))
    )
  )
  (nets
    (net (code "1") (name "/B0") (class "Default")
      (node (ref "D18") (pin "C") (pinfunction "C_C") (pintype "passive"))
      (node (ref "D22") (pin "C") (pinfunction "C_C") (pintype "passive"))
      (node (ref "D26") (pin "C") (pinfunction "C_C") (pintype "passive"))
      (node (ref "D4") (pin "C") (pinfunction "C_C") (pintype "passive"))
      (node (ref "T5") (pin "C") (pinfunction "C_C") (pintype "passive"))
    )
    (net (code "2") (name "/B1") (class "Default")
      (node (ref "D13") (pin "C") (pinfunction "C_C") (pintype "passive"))
      (node (ref "D23") (pin "C") (pinfunction "C_C") (pintype "passive"))
      (node (ref "D30") (pin "C") (pinfunction "C_C") (pintype "passive"))
      (node (ref "D5") (pin "C") (pinfunction "C_C") (pintype "passive"))
      (node (ref "D9") (pin "C") (pinfunction "C_C") (pintype "passive"))
      (node (ref "T6") (pin "C") (pinfunction "C_C") (pintype "passive"))
    )
    (net (code "3") (name "/B2") (class "Default")
      (node (ref "D16") (pin "C") (pinfunction "C_C") (pintype "passive"))
      (node (ref "D20") (pin "C") (pinfunction "C_C") (pintype "passive"))
      (node (ref "D28") (pin "C") (pinfunction "C_C") (pintype "passive"))
      (node (ref "D31") (pin "C") (pinfunction "C_C") (pintype "passive"))
      (node (ref "D37") (pin "C") (pinfunction "C_C") (pintype "passive"))
      (node (ref "T7") (pin "C") (pinfunction "C_C") (pintype "passive"))
    )
    (net (code "4") (name "/B3") (class "Default")
      (node (ref "D21") (pin "C") (pinfunction "C_C") (pintype "passive"))
      (node (ref "D25") (pin "C") (pinfunction "C_C") (pintype "passive"))
      (node (ref "D32") (pin "C") (pinfunction "C_C") (pintype "passive"))
      (node (ref "D38") (pin "C") (pinfunction "C_C") (pintype "passive"))
      (node (ref "D41") (pin "C") (pinfunction "C_C") (pintype "passive"))
      (node (ref "D44") (pin "C") (pinfunction "C_C") (pintype "passive"))
      (node (ref "T8") (pin "C") (pinfunction "C_C") (pintype "passive"))
    )
    (net (code "5") (name "/SEGA") (class "Default")
      (node (ref "R20") (pin "1") (pinfunction "1_1") (pintype "passive"))
      (node (ref "T9") (pin "C") (pinfunction "C_C") (pintype "passive"))
    )
    (net (code "6") (name "/SEGB") (class "Default")
      (node (ref "R21") (pin "1") (pinfunction "1_1") (pintype "passive"))
      (node (ref "T10") (pin "C") (pinfunction "C_C") (pintype "passive"))
    )
    (net (code "7") (name "/SEGC") (class "Default")
      (node (ref "R22") (pin "1") (pinfunction "1_1") (pintype "passive"))
      (node (ref "T11") (pin "C") (pinfunction "C_C") (pintype "passive"))
    )
    (net (code "8") (name "/SEGD") (class "Default")
      (node (ref "R23") (pin "1") (pinfunction "1_1") (pintype "passive"))
      (node (ref "T12") (pin "C") (pinfunction "C_C") (pintype "passive"))
    )
    (net (code "9") (name "/SEGE") (class "Default")
      (node (ref "R24") (pin "1") (pinfunction "1_1") (pintype "passive"))
      (node (ref "T13") (pin "C") (pinfunction "C_C") (pintype "passive"))
    )
    (net (code "10") (name "/SEGF") (class "Default")
      (node (ref "R25") (pin "1") (pinfunction "1_1") (pintype "passive"))
      (node (ref "T14") (pin "C") (pinfunction "C_C") (pintype "passive"))
    )
    (net (code "11") (name "/SEGG") (class "Default")
      (node (ref "R26") (pin "1") (pinfunction "1_1") (pintype "passive"))
      (node (ref "T15") (pin "C") (pinfunction "C_C") (pintype "passive"))
    )
    (net (code "12") (name "/{slash}B0") (class "Default")
      (node (ref "D1") (pin "C") (pinfunction "C_C") (pintype "passive"))
      (node (ref "D12") (pin "C") (pinfunction "C_C") (pintype "passive"))
      (node (ref "D15") (pin "C") (pinfunction "C_C") (pintype "passive"))
      (node (ref "D33") (pin "C") (pinfunction "C_C") (pintype "passive"))
      (node (ref "D36") (pin "C") (pinfunction "C_C") (pintype "passive"))
      (node (ref "D42") (pin "C") (pinfunction "C_C") (pintype "passive"))
      (node (ref "R5") (pin "1") (pinfunction "1_1") (pintype "passive"))
      (node (ref "R9") (pin "1") (pinfunction "1_1") (pintype "passive"))
      (node (ref "T1") (pin "C") (pinfunction "C_C") (pintype "passive"))
    )
    (net (code "13") (name "/{slash}B1") (class "Default")
      (node (ref "D19") (pin "C") (pinfunction "C_C") (pintype "passive"))
      (node (ref "D2") (pin "C") (pinfunction "C_C") (pintype "passive"))
      (node (ref "D27") (pin "C") (pinfunction "C_C") (pintype "passive"))
      (node (ref "D34") (pin "C") (pinfunction "C_C") (pintype "passive"))
      (node (ref "D39") (pin "C") (pinfunction "C_C") (pintype "passive"))
      (node (ref "D7") (pin "C") (pinfunction "C_C") (pintype "passive"))
      (node (ref "R10") (pin "1") (pinfunction "1_1") (pintype "passive"))
      (node (ref "R6") (pin "1") (pinfunction "1_1") (pintype "passive"))
      (node (ref "T2") (pin "C") (pinfunction "C_C") (pintype "passive"))
    )
    (net (code "14") (name "/{slash}B2") (class "Default")
      (node (ref "D10") (pin "C") (pinfunction "C_C") (pintype "passive"))
      (node (ref "D24") (pin "C") (pinfunction "C_C") (pintype "passive"))
      (node (ref "D35") (pin "C") (pinfunction "C_C") (pintype "passive"))
      (node (ref "D40") (pin "C") (pinfunction "C_C") (pintype "passive"))
      (node (ref "D43") (pin "C") (pinfunction "C_C") (pintype "passive"))
      (node (ref "D8") (pin "C") (pinfunction "C_C") (pintype "passive"))
      (node (ref "R11") (pin "1") (pinfunction "1_1") (pintype "passive"))
      (node (ref "R7") (pin "1") (pinfunction "1_1") (pintype "passive"))
      (node (ref "T3") (pin "C") (pinfunction "C_C") (pintype "passive"))
    )
    (net (code "15") (name "/{slash}B3") (class "Default")
      (node (ref "D11") (pin "C") (pinfunction "C_C") (pintype "passive"))
      (node (ref "D14") (pin "C") (pinfunction "C_C") (pintype "passive"))
      (node (ref "D17") (pin "C") (pinfunction "C_C") (pintype "passive"))
      (node (ref "D29") (pin "C") (pinfunction "C_C") (pintype "passive"))
      (node (ref "D3") (pin "C") (pinfunction "C_C") (pintype "passive"))
      (node (ref "D6") (pin "C") (pinfunction "C_C") (pintype "passive"))
      (node (ref "R12") (pin "1") (pinfunction "1_1") (pintype "passive"))
      (node (ref "R8") (pin "1") (pinfunction "1_1") (pintype "passive"))
      (node (ref "T4") (pin "C") (pinfunction "C_C") (pintype "passive"))
    )
    (net (code "16") (name "GND") (class "Default")
      (node (ref "T1") (pin "E") (pinfunction "E_E") (pintype "passive"))
      (node (ref "T10") (pin "E") (pinfunction "E_E") (pintype "passive"))
      (node (ref "T11") (pin "E") (pinfunction "E_E") (pintype "passive"))
      (node (ref "T12") (pin "E") (pinfunction "E_E") (pintype "passive"))
      (node (ref "T13") (pin "E") (pinfunction "E_E") (pintype "passive"))
      (node (ref "T14") (pin "E") (pinfunction "E_E") (pintype "passive"))
      (node (ref "T15") (pin "E") (pinfunction "E_E") (pintype "passive"))
      (node (ref "T18") (pin "E") (pinfunction "E_E") (pintype "passive"))
      (node (ref "T2") (pin "E") (pinfunction "E_E") (pintype "passive"))
      (node (ref "T21") (pin "E") (pinfunction "E_E") (pintype "passive"))
      (node (ref "T24") (pin "E") (pinfunction "E_E") (pintype "passive"))
      (node (ref "T27") (pin "E") (pinfunction "E_E") (pintype "passive"))
      (node (ref "T3") (pin "E") (pinfunction "E_E") (pintype "passive"))
      (node (ref "T30") (pin "E") (pinfunction "E_E") (pintype "passive"))
      (node (ref "T33") (pin "E") (pinfunction "E_E") (pintype "passive"))
      (node (ref "T4") (pin "E") (pinfunction "E_E") (pintype "passive"))
      (node (ref "T45") (pin "E") (pinfunction "E_E") (pintype "passive"))
      (node (ref "T46") (pin "E") (pinfunction "E_E") (pintype "passive"))
      (node (ref "T47") (pin "E") (pinfunction "E_E") (pintype "passive"))
      (node (ref "T48") (pin "E") (pinfunction "E_E") (pintype "passive"))
      (node (ref "T49") (pin "E") (pinfunction "E_E") (pintype "passive"))
      (node (ref "T5") (pin "E") (pinfunction "E_E") (pintype "passive"))
      (node (ref "T50") (pin "E") (pinfunction "E_E") (pintype "passive"))
      (node (ref "T6") (pin "E") (pinfunction "E_E") (pintype "passive"))
      (node (ref "T7") (pin "E") (pinfunction "E_E") (pintype "passive"))
      (node (ref "T8") (pin "E") (pinfunction "E_E") (pintype "passive"))
      (node (ref "T9") (pin "E") (pinfunction "E_E") (pintype "passive"))
    )
    (net (code "17") (name "Net-(D1-PadA)") (class "Default")
      (node (ref "D1") (pin "A") (pinfunction "A_A") (pintype "passive"))
      (node (ref "D2") (pin "A") (pinfunction "A_A") (pintype "passive"))
      (node (ref "D3") (pin "A") (pinfunction "A_A") (pintype "passive"))
      (node (ref "D53") (pin "A") (pinfunction "A_A") (pintype "passive"))
      (node (ref "R58") (pin "2") (pinfunction "2_2") (pintype "passive"))
    )
    (net (code "18") (name "Net-(D4-PadA)") (class "Default")
      (node (ref "D4") (pin "A") (pinfunction "A_A") (pintype "passive"))
      (node (ref "D45") (pin "A") (pinfunction "A_A") (pintype "passive"))
      (node (ref "D5") (pin "A") (pinfunction "A_A") (pintype "passive"))
      (node (ref "D54") (pin "A") (pinfunction "A_A") (pintype "passive"))
      (node (ref "D59") (pin "A") (pinfunction "A_A") (pintype "passive"))
      (node (ref "D6") (pin "A") (pinfunction "A_A") (pintype "passive"))
      (node (ref "R57") (pin "2") (pinfunction "2_2") (pintype "passive"))
    )
    (net (code "19") (name "Net-(D10-PadA)") (class "Default")
      (node (ref "D10") (pin "A") (pinfunction "A_A") (pintype "passive"))
      (node (ref "D11") (pin "A") (pinfunction "A_A") (pintype "passive"))
      (node (ref "D56") (pin "A") (pinfunction "A_A") (pintype "passive"))
      (node (ref "D66") (pin "A") (pinfunction "A_A") (pintype "passive"))
      (node (ref "D89") (pin "A") (pinfunction "A_A") (pintype "passive"))
      (node (ref "D9") (pin "A") (pinfunction "A_A") (pintype "passive"))
      (node (ref "R54") (pin "2") (pinfunction "2_2") (pintype "passive"))
    )
    (net (code "20") (name "Net-(D12-PadA)") (class "Default")
      (node (ref "D12") (pin "A") (pinfunction "A_A") (pintype "passive"))
      (node (ref "D13") (pin "A") (pinfunction "A_A") (pintype "passive"))
      (node (ref "D14") (pin "A") (pinfunction "A_A") (pintype "passive"))
      (node (ref "D46") (pin "A") (pinfunction "A_A") (pintype "passive"))
      (node (ref "D67") (pin "A") (pinfunction "A_A") (pintype "passive"))
      (node (ref "D74") (pin "A") (pinfunction "A_A") (pintype "passive"))
      (node (ref "R53") (pin "2") (pinfunction "2_2") (pintype "passive"))
    )
    (net (code "21") (name "Net-(D15-PadA)") (class "Default")
      (node (ref "D15") (pin "A") (pinfunction "A_A") (pintype "passive"))
      (node (ref "D16") (pin "A") (pinfunction "A_A") (pintype "passive"))
      (node (ref "D17") (pin "A") (pinfunction "A_A") (pintype "passive"))
      (node (ref "D61") (pin "A") (pinfunction "A_A") (pintype "passive"))
      (node (ref "D81") (pin "A") (pinfunction "A_A") (pintype "passive"))
      (node (ref "D90") (pin "A") (pinfunction "A_A") (pintype "passive"))
      (node (ref "R52") (pin "2") (pinfunction "2_2") (pintype "passive"))
    )
    (net (code "22") (name "Net-(D18-PadA)") (class "Default")
      (node (ref "D18") (pin "A") (pinfunction "A_A") (pintype "passive"))
      (node (ref "D19") (pin "A") (pinfunction "A_A") (pintype "passive"))
      (node (ref "D20") (pin "A") (pinfunction "A_A") (pintype "passive"))
      (node (ref "D21") (pin "A") (pinfunction "A_A") (pintype "passive"))
      (node (ref "D57") (pin "A") (pinfunction "A_A") (pintype "passive"))
      (node (ref "D62") (pin "A") (pinfunction "A_A") (pintype "passive"))
      (node (ref "D68") (pin "A") (pinfunction "A_A") (pintype "passive"))
      (node (ref "D75") (pin "A") (pinfunction "A_A") (pintype "passive"))
      (node (ref "D91") (pin "A") (pinfunction "A_A") (pintype "passive"))
      (node (ref "R50") (pin "2") (pinfunction "2_2") (pintype "passive"))
    )
    (net (code "23") (name "Net-(D22-PadA)") (class "Default")
      (node (ref "D22") (pin "A") (pinfunction "A_A") (pintype "passive"))
      (node (ref "D23") (pin "A") (pinfunction "A_A") (pintype "passive"))
      (node (ref "D24") (pin "A") (pinfunction "A_A") (pintype "passive"))
      (node (ref "D25") (pin "A") (pinfunction "A_A") (pintype "passive"))
      (node (ref "D63") (pin "A") (pinfunction "A_A") (pintype "passive"))
      (node (ref "D69") (pin "A") (pinfunction "A_A") (pintype "passive"))
      (node (ref "D76") (pin "A") (pinfunction "A_A") (pintype "passive"))
      (node (ref "D82") (pin "A") (pinfunction "A_A") (pintype "passive"))
      (node (ref "D92") (pin "A") (pinfunction "A_A") (pintype "passive"))
      (node (ref "R49") (pin "2") (pinfunction "2_2") (pintype "passive"))
    )
    (net (code "24") (name "Net-(D26-PadA)") (class "Default")
      (node (ref "D26") (pin "A") (pinfunction "A_A") (pintype "passive"))
      (node (ref "D27") (pin "A") (pinfunction "A_A") (pintype "passive"))
      (node (ref "D28") (pin "A") (pinfunction "A_A") (pintype "passive"))
      (node (ref "D29") (pin "A") (pinfunction "A_A") (pintype "passive"))
      (node (ref "D47") (pin "A") (pinfunction "A_A") (pintype "passive"))
      (node (ref "D64") (pin "A") (pinfunction "A_A") (pintype "passive"))
      (node (ref "D70") (pin "A") (pinfunction "A_A") (pintype "passive"))
      (node (ref "D83") (pin "A") (pinfunction "A_A") (pintype "passive"))
      (node (ref "D93") (pin "A") (pinfunction "A_A") (pintype "passive"))
      (node (ref "R48") (pin "2") (pinfunction "2_2") (pintype "passive"))
    )
    (net (code "25") (name "Net-(D30-PadA)") (class "Default")
      (node (ref "D30") (pin "A") (pinfunction "A_A") (pintype "passive"))
      (node (ref "D31") (pin "A") (pinfunction "A_A") (pintype "passive"))
      (node (ref "D32") (pin "A") (pinfunction "A_A") (pintype "passive"))
      (node (ref "D48") (pin "A") (pinfunction "A_A") (pintype "passive"))
      (node (ref "D77") (pin "A") (pinfunction "A_A") (pintype "passive"))
      (node (ref "D84") (pin "A") (pinfunction "A_A") (pintype "passive"))
      (node (ref "D94") (pin "A") (pinfunction "A_A") (pintype "passive"))
      (node (ref "R46") (pin "2") (pinfunction "2_2") (pintype "passive"))
    )
    (net (code "26") (name "Net-(D33-PadA)") (class "Default")
      (node (ref "D33") (pin "A") (pinfunction "A_A") (pintype "passive"))
      (node (ref "D34") (pin "A") (pinfunction "A_A") (pintype "passive"))
      (node (ref "D35") (pin "A") (pinfunction "A_A") (pintype "passive"))
      (node (ref "D49") (pin "A") (pinfunction "A_A") (pintype "passive"))
      (node (ref "D71") (pin "A") (pinfunction "A_A") (pintype "passive"))
      (node (ref "D78") (pin "A") (pinfunction "A_A") (pintype "passive"))
      (node (ref "D85") (pin "A") (pinfunction "A_A") (pintype "passive"))
      (node (ref "R45") (pin "2") (pinfunction "2_2") (pintype "passive"))
    )
    (net (code "27") (name "Net-(D36-PadA)") (class "Default")
      (node (ref "D36") (pin "A") (pinfunction "A_A") (pintype "passive"))
      (node (ref "D37") (pin "A") (pinfunction "A_A") (pintype "passive"))
      (node (ref "D38") (pin "A") (pinfunction "A_A") (pintype "passive"))
      (node (ref "D50") (pin "A") (pinfunction "A_A") (pintype "passive"))
      (node (ref "D72") (pin "A") (pinfunction "A_A") (pintype "passive"))
      (node (ref "D79") (pin "A") (pinfunction "A_A") (pintype "passive"))
      (node (ref "D86") (pin "A") (pinfunction "A_A") (pintype "passive"))
      (node (ref "R44") (pin "2") (pinfunction "2_2") (pintype "passive"))
    )
    (net (code "28") (name "Net-(D39-PadA)") (class "Default")
      (node (ref "D39") (pin "A") (pinfunction "A_A") (pintype "passive"))
      (node (ref "D40") (pin "A") (pinfunction "A_A") (pintype "passive"))
      (node (ref "D41") (pin "A") (pinfunction "A_A") (pintype "passive"))
      (node (ref "D51") (pin "A") (pinfunction "A_A") (pintype "passive"))
      (node (ref "D73") (pin "A") (pinfunction "A_A") (pintype "passive"))
      (node (ref "D87") (pin "A") (pinfunction "A_A") (pintype "passive"))
      (node (ref "D95") (pin "A") (pinfunction "A_A") (pintype "passive"))
      (node (ref "R42") (pin "2") (pinfunction "2_2") (pintype "passive"))
    )
    (net (code "29") (name "Net-(D42-PadA)") (class "Default")
      (node (ref "D42") (pin "A") (pinfunction "A_A") (pintype "passive"))
      (node (ref "D43") (pin "A") (pinfunction "A_A") (pintype "passive"))
      (node (ref "D44") (pin "A") (pinfunction "A_A") (pintype "passive"))
      (node (ref "D52") (pin "A") (pinfunction "A_A") (pintype "passive"))
      (node (ref "D58") (pin "A") (pinfunction "A_A") (pintype "passive"))
      (node (ref "D65") (pin "A") (pinfunction "A_A") (pintype "passive"))
      (node (ref "D80") (pin "A") (pinfunction "A_A") (pintype "passive"))
      (node (ref "D88") (pin "A") (pinfunction "A_A") (pintype "passive"))
      (node (ref "D96") (pin "A") (pinfunction "A_A") (pintype "passive"))
      (node (ref "R41") (pin "2") (pinfunction "2_2") (pintype "passive"))
    )
    (net (code "30") (name "Net-(D45-PadC)") (class "Default")
      (node (ref "D45") (pin "C") (pinfunction "C_C") (pintype "passive"))
      (node (ref "D46") (pin "C") (pinfunction "C_C") (pintype "passive"))
      (node (ref "D47") (pin "C") (pinfunction "C_C") (pintype "passive"))
      (node (ref "D48") (pin "C") (pinfunction "C_C") (pintype "passive"))
      (node (ref "D49") (pin "C") (pinfunction "C_C") (pintype "passive"))
      (node (ref "D50") (pin "C") (pinfunction "C_C") (pintype "passive"))
      (node (ref "D51") (pin "C") (pinfunction "C_C") (pintype "passive"))
      (node (ref "D52") (pin "C") (pinfunction "C_C") (pintype "passive"))
      (node (ref "R13") (pin "1") (pinfunction "1_1") (pintype "passive"))
    )
    (net (code "31") (name "Net-(D53-PadC)") (class "Default")
      (node (ref "D53") (pin "C") (pinfunction "C_C") (pintype "passive"))
      (node (ref "D54") (pin "C") (pinfunction "C_C") (pintype "passive"))
      (node (ref "D55") (pin "C") (pinfunction "C_C") (pintype "passive"))
      (node (ref "D56") (pin "C") (pinfunction "C_C") (pintype "passive"))
      (node (ref "D57") (pin "C") (pinfunction "C_C") (pintype "passive"))
      (node (ref "D58") (pin "C") (pinfunction "C_C") (pintype "passive"))
      (node (ref "R14") (pin "1") (pinfunction "1_1") (pintype "passive"))
    )
    (net (code "32") (name "Net-(D55-PadA)") (class "Default")
      (node (ref "D55") (pin "A") (pinfunction "A_A") (pintype "passive"))
      (node (ref "D60") (pin "A") (pinfunction "A_A") (pintype "passive"))
      (node (ref "D7") (pin "A") (pinfunction "A_A") (pintype "passive"))
      (node (ref "D8") (pin "A") (pinfunction "A_A") (pintype "passive"))
      (node (ref "R56") (pin "2") (pinfunction "2_2") (pintype "passive"))
    )
    (net (code "33") (name "Net-(D59-PadC)") (class "Default")
      (node (ref "D59") (pin "C") (pinfunction "C_C") (pintype "passive"))
      (node (ref "D60") (pin "C") (pinfunction "C_C") (pintype "passive"))
      (node (ref "D61") (pin "C") (pinfunction "C_C") (pintype "passive"))
      (node (ref "D62") (pin "C") (pinfunction "C_C") (pintype "passive"))
      (node (ref "D63") (pin "C") (pinfunction "C_C") (pintype "passive"))
      (node (ref "D64") (pin "C") (pinfunction "C_C") (pintype "passive"))
      (node (ref "D65") (pin "C") (pinfunction "C_C") (pintype "passive"))
      (node (ref "R15") (pin "1") (pinfunction "1_1") (pintype "passive"))
    )
    (net (code "34") (name "Net-(D66-PadC)") (class "Default")
      (node (ref "D66") (pin "C") (pinfunction "C_C") (pintype "passive"))
      (node (ref "D67") (pin "C") (pinfunction "C_C") (pintype "passive"))
      (node (ref "D68") (pin "C") (pinfunction "C_C") (pintype "passive"))
      (node (ref "D69") (pin "C") (pinfunction "C_C") (pintype "passive"))
      (node (ref "D70") (pin "C") (pinfunction "C_C") (pintype "passive"))
      (node (ref "D71") (pin "C") (pinfunction "C_C") (pintype "passive"))
      (node (ref "D72") (pin "C") (pinfunction "C_C") (pintype "passive"))
      (node (ref "D73") (pin "C") (pinfunction "C_C") (pintype "passive"))
      (node (ref "R16") (pin "1") (pinfunction "1_1") (pintype "passive"))
    )
    (net (code "35") (name "Net-(D74-PadC)") (class "Default")
      (node (ref "D74") (pin "C") (pinfunction "C_C") (pintype "passive"))
      (node (ref "D75") (pin "C") (pinfunction "C_C") (pintype "passive"))
      (node (ref "D76") (pin "C") (pinfunction "C_C") (pintype "passive"))
      (node (ref "D77") (pin "C") (pinfunction "C_C") (pintype "passive"))
      (node (ref "D78") (pin "C") (pinfunction "C_C") (pintype "passive"))
      (node (ref "D79") (pin "C") (pinfunction "C_C") (pintype "passive"))
      (node (ref "D80") (pin "C") (pinfunction "C_C") (pintype "passive"))
      (node (ref "R17") (pin "1") (pinfunction "1_1") (pintype "passive"))
    )
    (net (code "36") (name "Net-(D81-PadC)") (class "Default")
      (node (ref "D81") (pin "C") (pinfunction "C_C") (pintype "passive"))
      (node (ref "D82") (pin "C") (pinfunction "C_C") (pintype "passive"))
      (node (ref "D83") (pin "C") (pinfunction "C_C") (pintype "passive"))
      (node (ref "D84") (pin "C") (pinfunction "C_C") (pintype "passive"))
      (node (ref "D85") (pin "C") (pinfunction "C_C") (pintype "passive"))
      (node (ref "D86") (pin "C") (pinfunction "C_C") (pintype "passive"))
      (node (ref "D87") (pin "C") (pinfunction "C_C") (pintype "passive"))
      (node (ref "D88") (pin "C") (pinfunction "C_C") (pintype "passive"))
      (node (ref "R18") (pin "1") (pinfunction "1_1") (pintype "passive"))
    )
    (net (code "37") (name "Net-(D89-PadC)") (class "Default")
      (node (ref "D89") (pin "C") (pinfunction "C_C") (pintype "passive"))
      (node (ref "D90") (pin "C") (pinfunction "C_C") (pintype "passive"))
      (node (ref "D91") (pin "C") (pinfunction "C_C") (pintype "passive"))
      (node (ref "D92") (pin "C") (pinfunction "C_C") (pintype "passive"))
      (node (ref "D93") (pin "C") (pinfunction "C_C") (pintype "passive"))
      (node (ref "D94") (pin "C") (pinfunction "C_C") (pintype "passive"))
      (node (ref "D95") (pin "C") (pinfunction "C_C") (pintype "passive"))
      (node (ref "D96") (pin "C") (pinfunction "C_C") (pintype "passive"))
      (node (ref "R19") (pin "1") (pinfunction "1_1") (pintype "passive"))
    )
    (net (code "38") (name "Net-(D97-PadC)") (class "Default")
      (node (ref "D97") (pin "C") (pinfunction "C_C") (pintype "passive"))
      (node (ref "J1A") (pin "1") (pinfunction "1_1") (pintype "passive"))
    )
    (net (code "39") (name "Net-(D98-PadC)") (class "Default")
      (node (ref "D98") (pin "C") (pinfunction "C_C") (pintype "passive"))
      (node (ref "J1A") (pin "2") (pinfunction "2_2") (pintype "passive"))
    )
    (net (code "40") (name "Net-(D99-PadC)") (class "Default")
      (node (ref "D99") (pin "C") (pinfunction "C_C") (pintype "passive"))
      (node (ref "J1A") (pin "3") (pinfunction "3_3") (pintype "passive"))
    )
    (net (code "41") (name "Net-(D100-PadA)") (class "Default")
      (node (ref "D100") (pin "A") (pinfunction "A_A") (pintype "passive"))
      (node (ref "D124") (pin "A") (pinfunction "A_A") (pintype "passive"))
      (node (ref "D163") (pin "A") (pinfunction "A_A") (pintype "passive"))
      (node (ref "R91") (pin "2") (pinfunction "2_2") (pintype "passive"))
    )
    (net (code "42") (name "Net-(D100-PadC)") (class "Default")
      (node (ref "D100") (pin "C") (pinfunction "C_C") (pintype "passive"))
      (node (ref "J1A") (pin "4") (pinfunction "4_4") (pintype "passive"))
    )
    (net (code "43") (name "Net-(D101-PadA)") (class "Default")
      (node (ref "D101") (pin "A") (pinfunction "A_A") (pintype "passive"))
      (node (ref "D125") (pin "A") (pinfunction "A_A") (pintype "passive"))
      (node (ref "D146") (pin "A") (pinfunction "A_A") (pintype "passive"))
      (node (ref "R92") (pin "2") (pinfunction "2_2") (pintype "passive"))
    )
    (net (code "44") (name "Net-(D101-PadC)") (class "Default")
      (node (ref "D101") (pin "C") (pinfunction "C_C") (pintype "passive"))
      (node (ref "J1A") (pin "5") (pinfunction "5_5") (pintype "passive"))
    )
    (net (code "45") (name "Net-(D102-PadA)") (class "Default")
      (node (ref "D102") (pin "A") (pinfunction "A_A") (pintype "passive"))
      (node (ref "D126") (pin "A") (pinfunction "A_A") (pintype "passive"))
      (node (ref "D152") (pin "A") (pinfunction "A_A") (pintype "passive"))
      (node (ref "R93") (pin "2") (pinfunction "2_2") (pintype "passive"))
    )
    (net (code "46") (name "Net-(D102-PadC)") (class "Default")
      (node (ref "D102") (pin "C") (pinfunction "C_C") (pintype "passive"))
      (node (ref "J1A") (pin "6") (pinfunction "6_6") (pintype "passive"))
    )
    (net (code "47") (name "Net-(D103-PadA)") (class "Default")
      (node (ref "D103") (pin "A") (pinfunction "A_A") (pintype "passive"))
      (node (ref "D127") (pin "A") (pinfunction "A_A") (pintype "passive"))
      (node (ref "D158") (pin "A") (pinfunction "A_A") (pintype "passive"))
      (node (ref "R94") (pin "2") (pinfunction "2_2") (pintype "passive"))
    )
    (net (code "48") (name "Net-(D103-PadC)") (class "Default")
      (node (ref "D103") (pin "C") (pinfunction "C_C") (pintype "passive"))
      (node (ref "J1A") (pin "7") (pinfunction "7_7") (pintype "passive"))
    )
    (net (code "49") (name "Net-(D104-PadA)") (class "Default")
      (node (ref "D104") (pin "A") (pinfunction "A_A") (pintype "passive"))
      (node (ref "D128") (pin "A") (pinfunction "A_A") (pintype "passive"))
      (node (ref "D164") (pin "A") (pinfunction "A_A") (pintype "passive"))
      (node (ref "R95") (pin "2") (pinfunction "2_2") (pintype "passive"))
    )
    (net (code "50") (name "Net-(D104-PadC)") (class "Default")
      (node (ref "D104") (pin "C") (pinfunction "C_C") (pintype "passive"))
      (node (ref "J1A") (pin "8") (pinfunction "8_8") (pintype "passive"))
    )
    (net (code "51") (name "Net-(D105-PadA)") (class "Default")
      (node (ref "D105") (pin "A") (pinfunction "A_A") (pintype "passive"))
      (node (ref "D129") (pin "A") (pinfunction "A_A") (pintype "passive"))
      (node (ref "D147") (pin "A") (pinfunction "A_A") (pintype "passive"))
      (node (ref "R96") (pin "2") (pinfunction "2_2") (pintype "passive"))
    )
    (net (code "52") (name "Net-(D105-PadC)") (class "Default")
      (node (ref "D105") (pin "C") (pinfunction "C_C") (pintype "passive"))
      (node (ref "J1B") (pin "1") (pinfunction "1_1") (pintype "passive"))
    )
    (net (code "53") (name "Net-(D106-PadA)") (class "Default")
      (node (ref "D106") (pin "A") (pinfunction "A_A") (pintype "passive"))
      (node (ref "D130") (pin "A") (pinfunction "A_A") (pintype "passive"))
      (node (ref "D155") (pin "A") (pinfunction "A_A") (pintype "passive"))
      (node (ref "R97") (pin "2") (pinfunction "2_2") (pintype "passive"))
    )
    (net (code "54") (name "Net-(D106-PadC)") (class "Default")
      (node (ref "D106") (pin "C") (pinfunction "C_C") (pintype "passive"))
      (node (ref "J1B") (pin "2") (pinfunction "2_2") (pintype "passive"))
    )
    (net (code "55") (name "Net-(D107-PadA)") (class "Default")
      (node (ref "D107") (pin "A") (pinfunction "A_A") (pintype "passive"))
      (node (ref "D131") (pin "A") (pinfunction "A_A") (pintype "passive"))
      (node (ref "D159") (pin "A") (pinfunction "A_A") (pintype "passive"))
      (node (ref "R98") (pin "2") (pinfunction "2_2") (pintype "passive"))
    )
    (net (code "56") (name "Net-(D107-PadC)") (class "Default")
      (node (ref "D107") (pin "C") (pinfunction "C_C") (pintype "passive"))
      (node (ref "J1B") (pin "3") (pinfunction "3_3") (pintype "passive"))
    )
    (net (code "57") (name "Net-(D108-PadA)") (class "Default")
      (node (ref "D108") (pin "A") (pinfunction "A_A") (pintype "passive"))
      (node (ref "D132") (pin "A") (pinfunction "A_A") (pintype "passive"))
      (node (ref "D165") (pin "A") (pinfunction "A_A") (pintype "passive"))
      (node (ref "R99") (pin "2") (pinfunction "2_2") (pintype "passive"))
    )
    (net (code "58") (name "Net-(D108-PadC)") (class "Default")
      (node (ref "D108") (pin "C") (pinfunction "C_C") (pintype "passive"))
      (node (ref "J1B") (pin "4") (pinfunction "4_4") (pintype "passive"))
    )
    (net (code "59") (name "Net-(D109-PadA)") (class "Default")
      (node (ref "D109") (pin "A") (pinfunction "A_A") (pintype "passive"))
      (node (ref "D133") (pin "A") (pinfunction "A_A") (pintype "passive"))
      (node (ref "D148") (pin "A") (pinfunction "A_A") (pintype "passive"))
      (node (ref "R100") (pin "2") (pinfunction "2_2") (pintype "passive"))
    )
    (net (code "60") (name "Net-(D109-PadC)") (class "Default")
      (node (ref "D109") (pin "C") (pinfunction "C_C") (pintype "passive"))
      (node (ref "J1B") (pin "5") (pinfunction "5_5") (pintype "passive"))
    )
    (net (code "61") (name "Net-(D110-PadA)") (class "Default")
      (node (ref "D110") (pin "A") (pinfunction "A_A") (pintype "passive"))
      (node (ref "D134") (pin "A") (pinfunction "A_A") (pintype "passive"))
      (node (ref "D156") (pin "A") (pinfunction "A_A") (pintype "passive"))
      (node (ref "R101") (pin "2") (pinfunction "2_2") (pintype "passive"))
    )
    (net (code "62") (name "Net-(D110-PadC)") (class "Default")
      (node (ref "D110") (pin "C") (pinfunction "C_C") (pintype "passive"))
      (node (ref "J1B") (pin "6") (pinfunction "6_6") (pintype "passive"))
    )
    (net (code "63") (name "Net-(D111-PadA)") (class "Default")
      (node (ref "D111") (pin "A") (pinfunction "A_A") (pintype "passive"))
      (node (ref "D135") (pin "A") (pinfunction "A_A") (pintype "passive"))
      (node (ref "D160") (pin "A") (pinfunction "A_A") (pintype "passive"))
      (node (ref "R102") (pin "2") (pinfunction "2_2") (pintype "passive"))
    )
    (net (code "64") (name "Net-(D111-PadC)") (class "Default")
      (node (ref "D111") (pin "C") (pinfunction "C_C") (pintype "passive"))
      (node (ref "J1B") (pin "7") (pinfunction "7_7") (pintype "passive"))
    )
    (net (code "65") (name "Net-(D112-PadA)") (class "Default")
      (node (ref "D112") (pin "A") (pinfunction "A_A") (pintype "passive"))
      (node (ref "D136") (pin "A") (pinfunction "A_A") (pintype "passive"))
      (node (ref "D166") (pin "A") (pinfunction "A_A") (pintype "passive"))
      (node (ref "R103") (pin "2") (pinfunction "2_2") (pintype "passive"))
    )
    (net (code "66") (name "Net-(D112-PadC)") (class "Default")
      (node (ref "D112") (pin "C") (pinfunction "C_C") (pintype "passive"))
      (node (ref "J1B") (pin "8") (pinfunction "8_8") (pintype "passive"))
    )
    (net (code "67") (name "Net-(D113-PadA)") (class "Default")
      (node (ref "D113") (pin "A") (pinfunction "A_A") (pintype "passive"))
      (node (ref "D137") (pin "A") (pinfunction "A_A") (pintype "passive"))
      (node (ref "D149") (pin "A") (pinfunction "A_A") (pintype "passive"))
      (node (ref "R104") (pin "2") (pinfunction "2_2") (pintype "passive"))
    )
    (net (code "68") (name "Net-(D113-PadC)") (class "Default")
      (node (ref "D113") (pin "C") (pinfunction "C_C") (pintype "passive"))
      (node (ref "J1C") (pin "1") (pinfunction "1_1") (pintype "passive"))
    )
    (net (code "69") (name "Net-(D114-PadA)") (class "Default")
      (node (ref "D114") (pin "A") (pinfunction "A_A") (pintype "passive"))
      (node (ref "D138") (pin "A") (pinfunction "A_A") (pintype "passive"))
      (node (ref "D153") (pin "A") (pinfunction "A_A") (pintype "passive"))
      (node (ref "R105") (pin "2") (pinfunction "2_2") (pintype "passive"))
    )
    (net (code "70") (name "Net-(D114-PadC)") (class "Default")
      (node (ref "D114") (pin "C") (pinfunction "C_C") (pintype "passive"))
      (node (ref "J1C") (pin "2") (pinfunction "2_2") (pintype "passive"))
    )
    (net (code "71") (name "Net-(D115-PadA)") (class "Default")
      (node (ref "D115") (pin "A") (pinfunction "A_A") (pintype "passive"))
      (node (ref "D139") (pin "A") (pinfunction "A_A") (pintype "passive"))
      (node (ref "D161") (pin "A") (pinfunction "A_A") (pintype "passive"))
      (node (ref "R106") (pin "2") (pinfunction "2_2") (pintype "passive"))
    )
    (net (code "72") (name "Net-(D115-PadC)") (class "Default")
      (node (ref "D115") (pin "C") (pinfunction "C_C") (pintype "passive"))
      (node (ref "J1C") (pin "3") (pinfunction "3_3") (pintype "passive"))
    )
    (net (code "73") (name "Net-(D116-PadA)") (class "Default")
      (node (ref "D116") (pin "A") (pinfunction "A_A") (pintype "passive"))
      (node (ref "D140") (pin "A") (pinfunction "A_A") (pintype "passive"))
      (node (ref "D167") (pin "A") (pinfunction "A_A") (pintype "passive"))
      (node (ref "R107") (pin "2") (pinfunction "2_2") (pintype "passive"))
    )
    (net (code "74") (name "Net-(D116-PadC)") (class "Default")
      (node (ref "D116") (pin "C") (pinfunction "C_C") (pintype "passive"))
      (node (ref "J1C") (pin "4") (pinfunction "4_4") (pintype "passive"))
    )
    (net (code "75") (name "Net-(D117-PadA)") (class "Default")
      (node (ref "D117") (pin "A") (pinfunction "A_A") (pintype "passive"))
      (node (ref "D141") (pin "A") (pinfunction "A_A") (pintype "passive"))
      (node (ref "D150") (pin "A") (pinfunction "A_A") (pintype "passive"))
      (node (ref "R108") (pin "2") (pinfunction "2_2") (pintype "passive"))
    )
    (net (code "76") (name "Net-(D117-PadC)") (class "Default")
      (node (ref "D117") (pin "C") (pinfunction "C_C") (pintype "passive"))
      (node (ref "J1C") (pin "5") (pinfunction "5_5") (pintype "passive"))
    )
    (net (code "77") (name "Net-(D118-PadA)") (class "Default")
      (node (ref "D118") (pin "A") (pinfunction "A_A") (pintype "passive"))
      (node (ref "D142") (pin "A") (pinfunction "A_A") (pintype "passive"))
      (node (ref "D154") (pin "A") (pinfunction "A_A") (pintype "passive"))
      (node (ref "R109") (pin "2") (pinfunction "2_2") (pintype "passive"))
    )
    (net (code "78") (name "Net-(D118-PadC)") (class "Default")
      (node (ref "D118") (pin "C") (pinfunction "C_C") (pintype "passive"))
      (node (ref "J1C") (pin "6") (pinfunction "6_6") (pintype "passive"))
    )
    (net (code "79") (name "Net-(D119-PadA)") (class "Default")
      (node (ref "D119") (pin "A") (pinfunction "A_A") (pintype "passive"))
      (node (ref "D143") (pin "A") (pinfunction "A_A") (pintype "passive"))
      (node (ref "D162") (pin "A") (pinfunction "A_A") (pintype "passive"))
      (node (ref "R110") (pin "2") (pinfunction "2_2") (pintype "passive"))
    )
    (net (code "80") (name "Net-(D119-PadC)") (class "Default")
      (node (ref "D119") (pin "C") (pinfunction "C_C") (pintype "passive"))
      (node (ref "J1C") (pin "7") (pinfunction "7_7") (pintype "passive"))
    )
    (net (code "81") (name "Net-(D120-PadA)") (class "Default")
      (node (ref "D120") (pin "A") (pinfunction "A_A") (pintype "passive"))
      (node (ref "D144") (pin "A") (pinfunction "A_A") (pintype "passive"))
      (node (ref "D168") (pin "A") (pinfunction "A_A") (pintype "passive"))
      (node (ref "R111") (pin "2") (pinfunction "2_2") (pintype "passive"))
    )
    (net (code "82") (name "Net-(D120-PadC)") (class "Default")
      (node (ref "D120") (pin "C") (pinfunction "C_C") (pintype "passive"))
      (node (ref "J1C") (pin "8") (pinfunction "8_8") (pintype "passive"))
    )
    (net (code "83") (name "Net-(D121-PadA)") (class "Default")
      (node (ref "D121") (pin "A") (pinfunction "A_A") (pintype "passive"))
      (node (ref "D145") (pin "A") (pinfunction "A_A") (pintype "passive"))
      (node (ref "D97") (pin "A") (pinfunction "A_A") (pintype "passive"))
      (node (ref "R88") (pin "2") (pinfunction "2_2") (pintype "passive"))
    )
    (net (code "84") (name "Net-(D121-PadC)") (class "Default")
      (node (ref "D121") (pin "C") (pinfunction "C_C") (pintype "passive"))
      (node (ref "D122") (pin "C") (pinfunction "C_C") (pintype "passive"))
      (node (ref "D123") (pin "C") (pinfunction "C_C") (pintype "passive"))
      (node (ref "D124") (pin "C") (pinfunction "C_C") (pintype "passive"))
      (node (ref "R87") (pin "1") (pinfunction "1_1") (pintype "passive"))
      (node (ref "T18") (pin "C") (pinfunction "C_C") (pintype "passive"))
    )
    (net (code "85") (name "Net-(D122-PadA)") (class "Default")
      (node (ref "D122") (pin "A") (pinfunction "A_A") (pintype "passive"))
      (node (ref "D151") (pin "A") (pinfunction "A_A") (pintype "passive"))
      (node (ref "D98") (pin "A") (pinfunction "A_A") (pintype "passive"))
      (node (ref "R89") (pin "2") (pinfunction "2_2") (pintype "passive"))
    )
    (net (code "86") (name "Net-(D123-PadA)") (class "Default")
      (node (ref "D123") (pin "A") (pinfunction "A_A") (pintype "passive"))
      (node (ref "D157") (pin "A") (pinfunction "A_A") (pintype "passive"))
      (node (ref "D99") (pin "A") (pinfunction "A_A") (pintype "passive"))
      (node (ref "R90") (pin "2") (pinfunction "2_2") (pintype "passive"))
    )
    (net (code "87") (name "Net-(D125-PadC)") (class "Default")
      (node (ref "D125") (pin "C") (pinfunction "C_C") (pintype "passive"))
      (node (ref "D126") (pin "C") (pinfunction "C_C") (pintype "passive"))
      (node (ref "D127") (pin "C") (pinfunction "C_C") (pintype "passive"))
      (node (ref "D128") (pin "C") (pinfunction "C_C") (pintype "passive"))
      (node (ref "R86") (pin "1") (pinfunction "1_1") (pintype "passive"))
      (node (ref "T21") (pin "C") (pinfunction "C_C") (pintype "passive"))
    )
    (net (code "88") (name "Net-(D129-PadC)") (class "Default")
      (node (ref "D129") (pin "C") (pinfunction "C_C") (pintype "passive"))
      (node (ref "D130") (pin "C") (pinfunction "C_C") (pintype "passive"))
      (node (ref "D131") (pin "C") (pinfunction "C_C") (pintype "passive"))
      (node (ref "D132") (pin "C") (pinfunction "C_C") (pintype "passive"))
      (node (ref "R85") (pin "1") (pinfunction "1_1") (pintype "passive"))
      (node (ref "T24") (pin "C") (pinfunction "C_C") (pintype "passive"))
    )
    (net (code "89") (name "Net-(D133-PadC)") (class "Default")
      (node (ref "D133") (pin "C") (pinfunction "C_C") (pintype "passive"))
      (node (ref "D134") (pin "C") (pinfunction "C_C") (pintype "passive"))
      (node (ref "D135") (pin "C") (pinfunction "C_C") (pintype "passive"))
      (node (ref "D136") (pin "C") (pinfunction "C_C") (pintype "passive"))
      (node (ref "R84") (pin "1") (pinfunction "1_1") (pintype "passive"))
      (node (ref "T27") (pin "C") (pinfunction "C_C") (pintype "passive"))
    )
    (net (code "90") (name "Net-(D137-PadC)") (class "Default")
      (node (ref "D137") (pin "C") (pinfunction "C_C") (pintype "passive"))
      (node (ref "D138") (pin "C") (pinfunction "C_C") (pintype "passive"))
      (node (ref "D139") (pin "C") (pinfunction "C_C") (pintype "passive"))
      (node (ref "D140") (pin "C") (pinfunction "C_C") (pintype "passive"))
      (node (ref "R83") (pin "1") (pinfunction "1_1") (pintype "passive"))
      (node (ref "T30") (pin "C") (pinfunction "C_C") (pintype "passive"))
    )
    (net (code "91") (name "Net-(D141-PadC)") (class "Default")
      (node (ref "D141") (pin "C") (pinfunction "C_C") (pintype "passive"))
      (node (ref "D142") (pin "C") (pinfunction "C_C") (pintype "passive"))
      (node (ref "D143") (pin "C") (pinfunction "C_C") (pintype "passive"))
      (node (ref "D144") (pin "C") (pinfunction "C_C") (pintype "passive"))
      (node (ref "R82") (pin "1") (pinfunction "1_1") (pintype "passive"))
      (node (ref "T33") (pin "C") (pinfunction "C_C") (pintype "passive"))
    )
    (net (code "92") (name "Net-(D145-PadC)") (class "Default")
      (node (ref "D145") (pin "C") (pinfunction "C_C") (pintype "passive"))
      (node (ref "D146") (pin "C") (pinfunction "C_C") (pintype "passive"))
      (node (ref "D147") (pin "C") (pinfunction "C_C") (pintype "passive"))
      (node (ref "D148") (pin "C") (pinfunction "C_C") (pintype "passive"))
      (node (ref "D149") (pin "C") (pinfunction "C_C") (pintype "passive"))
      (node (ref "D150") (pin "C") (pinfunction "C_C") (pintype "passive"))
      (node (ref "R1") (pin "1") (pinfunction "1_1") (pintype "passive"))
    )
    (net (code "93") (name "Net-(D151-PadC)") (class "Default")
      (node (ref "D151") (pin "C") (pinfunction "C_C") (pintype "passive"))
      (node (ref "D152") (pin "C") (pinfunction "C_C") (pintype "passive"))
      (node (ref "D153") (pin "C") (pinfunction "C_C") (pintype "passive"))
      (node (ref "D154") (pin "C") (pinfunction "C_C") (pintype "passive"))
      (node (ref "D155") (pin "C") (pinfunction "C_C") (pintype "passive"))
      (node (ref "D156") (pin "C") (pinfunction "C_C") (pintype "passive"))
      (node (ref "R2") (pin "1") (pinfunction "1_1") (pintype "passive"))
    )
    (net (code "94") (name "Net-(D157-PadC)") (class "Default")
      (node (ref "D157") (pin "C") (pinfunction "C_C") (pintype "passive"))
      (node (ref "D158") (pin "C") (pinfunction "C_C") (pintype "passive"))
      (node (ref "D159") (pin "C") (pinfunction "C_C") (pintype "passive"))
      (node (ref "D160") (pin "C") (pinfunction "C_C") (pintype "passive"))
      (node (ref "D161") (pin "C") (pinfunction "C_C") (pintype "passive"))
      (node (ref "D162") (pin "C") (pinfunction "C_C") (pintype "passive"))
      (node (ref "R3") (pin "1") (pinfunction "1_1") (pintype "passive"))
    )
    (net (code "95") (name "Net-(D163-PadC)") (class "Default")
      (node (ref "D163") (pin "C") (pinfunction "C_C") (pintype "passive"))
      (node (ref "D164") (pin "C") (pinfunction "C_C") (pintype "passive"))
      (node (ref "D165") (pin "C") (pinfunction "C_C") (pintype "passive"))
      (node (ref "D166") (pin "C") (pinfunction "C_C") (pintype "passive"))
      (node (ref "D167") (pin "C") (pinfunction "C_C") (pintype "passive"))
      (node (ref "D168") (pin "C") (pinfunction "C_C") (pintype "passive"))
      (node (ref "R4") (pin "1") (pinfunction "1_1") (pintype "passive"))
    )
    (net (code "96") (name "Net-(DISP1-A)") (class "Default")
      (node (ref "DISP1") (pin "7") (pinfunction "A_7") (pintype "passive"))
      (node (ref "R20") (pin "2") (pinfunction "2_2") (pintype "passive"))
    )
    (net (code "97") (name "Net-(DISP1-B)") (class "Default")
      (node (ref "DISP1") (pin "6") (pinfunction "B_6") (pintype "passive"))
      (node (ref "R21") (pin "2") (pinfunction "2_2") (pintype "passive"))
    )
    (net (code "98") (name "Net-(DISP1-C)") (class "Default")
      (node (ref "DISP1") (pin "4") (pinfunction "C_4") (pintype "passive"))
      (node (ref "R22") (pin "2") (pinfunction "2_2") (pintype "passive"))
    )
    (net (code "99") (name "Net-(DISP1-CA1)") (class "Default")
      (node (ref "DISP1") (pin "3") (pinfunction "CA1_3") (pintype "passive"))
      (node (ref "DISP1") (pin "8") (pinfunction "CA2_8") (pintype "passive"))
      (node (ref "T44") (pin "C") (pinfunction "C_C") (pintype "passive"))
    )
    (net (code "100") (name "Net-(DISP1-D)") (class "Default")
      (node (ref "DISP1") (pin "2") (pinfunction "D_2") (pintype "passive"))
      (node (ref "R23") (pin "2") (pinfunction "2_2") (pintype "passive"))
    )
    (net (code "101") (name "Net-(DISP1-E)") (class "Default")
      (node (ref "DISP1") (pin "1") (pinfunction "E_1") (pintype "passive"))
      (node (ref "R24") (pin "2") (pinfunction "2_2") (pintype "passive"))
    )
    (net (code "102") (name "Net-(DISP1-F)") (class "Default")
      (node (ref "DISP1") (pin "9") (pinfunction "F_9") (pintype "passive"))
      (node (ref "R25") (pin "2") (pinfunction "2_2") (pintype "passive"))
    )
    (net (code "103") (name "Net-(DISP1-G)") (class "Default")
      (node (ref "DISP1") (pin "10") (pinfunction "G_10") (pintype "passive"))
      (node (ref "R26") (pin "2") (pinfunction "2_2") (pintype "passive"))
    )
    (net (code "104") (name "Net-(R1-Pad2)") (class "Default")
      (node (ref "R1") (pin "2") (pinfunction "2_2") (pintype "passive"))
      (node (ref "T1") (pin "B") (pinfunction "B_B") (pintype "passive"))
    )
    (net (code "105") (name "Net-(R2-Pad2)") (class "Default")
      (node (ref "R2") (pin "2") (pinfunction "2_2") (pintype "passive"))
      (node (ref "T2") (pin "B") (pinfunction "B_B") (pintype "passive"))
    )
    (net (code "106") (name "Net-(R3-Pad2)") (class "Default")
      (node (ref "R3") (pin "2") (pinfunction "2_2") (pintype "passive"))
      (node (ref "T3") (pin "B") (pinfunction "B_B") (pintype "passive"))
    )
    (net (code "107") (name "Net-(R4-Pad2)") (class "Default")
      (node (ref "R4") (pin "2") (pinfunction "2_2") (pintype "passive"))
      (node (ref "T4") (pin "B") (pinfunction "B_B") (pintype "passive"))
    )
    (net (code "108") (name "Net-(R9-Pad2)") (class "Default")
      (node (ref "R9") (pin "2") (pinfunction "2_2") (pintype "passive"))
      (node (ref "T5") (pin "B") (pinfunction "B_B") (pintype "passive"))
    )
    (net (code "109") (name "Net-(R10-Pad2)") (class "Default")
      (node (ref "R10") (pin "2") (pinfunction "2_2") (pintype "passive"))
      (node (ref "T6") (pin "B") (pinfunction "B_B") (pintype "passive"))
    )
    (net (code "110") (name "Net-(R11-Pad2)") (class "Default")
      (node (ref "R11") (pin "2") (pinfunction "2_2") (pintype "passive"))
      (node (ref "T7") (pin "B") (pinfunction "B_B") (pintype "passive"))
    )
    (net (code "111") (name "Net-(R12-Pad2)") (class "Default")
      (node (ref "R12") (pin "2") (pinfunction "2_2") (pintype "passive"))
      (node (ref "T8") (pin "B") (pinfunction "B_B") (pintype "passive"))
    )
    (net (code "112") (name "Net-(R13-Pad2)") (class "Default")
      (node (ref "R13") (pin "2") (pinfunction "2_2") (pintype "passive"))
      (node (ref "T9") (pin "B") (pinfunction "B_B") (pintype "passive"))
    )
    (net (code "113") (name "Net-(R14-Pad2)") (class "Default")
      (node (ref "R14") (pin "2") (pinfunction "2_2") (pintype "passive"))
      (node (ref "T10") (pin "B") (pinfunction "B_B") (pintype "passive"))
    )
    (net (code "114") (name "Net-(R15-Pad2)") (class "Default")
      (node (ref "R15") (pin "2") (pinfunction "2_2") (pintype "passive"))
      (node (ref "T11") (pin "B") (pinfunction "B_B") (pintype "passive"))
    )
    (net (code "115") (name "Net-(R16-Pad2)") (class "Default")
      (node (ref "R16") (pin "2") (pinfunction "2_2") (pintype "passive"))
      (node (ref "T12") (pin "B") (pinfunction "B_B") (pintype "passive"))
    )
    (net (code "116") (name "Net-(R17-Pad2)") (class "Default")
      (node (ref "R17") (pin "2") (pinfunction "2_2") (pintype "passive"))
      (node (ref "T13") (pin "B") (pinfunction "B_B") (pintype "passive"))
    )
    (net (code "117") (name "Net-(R18-Pad2)") (class "Default")
      (node (ref "R18") (pin "2") (pinfunction "2_2") (pintype "passive"))
      (node (ref "T14") (pin "B") (pinfunction "B_B") (pintype "passive"))
    )
    (net (code "118") (name "Net-(R19-Pad2)") (class "Default")
      (node (ref "R19") (pin "2") (pinfunction "2_2") (pintype "passive"))
      (node (ref "T15") (pin "B") (pinfunction "B_B") (pintype "passive"))
    )
    (net (code "119") (name "Net-(R43-Pad1)") (class "Default")
      (node (ref "R43") (pin "1") (pinfunction "1_1") (pintype "passive"))
      (node (ref "T18") (pin "B") (pinfunction "B_B") (pintype "passive"))
    )
    (net (code "120") (name "Net-(R47-Pad1)") (class "Default")
      (node (ref "R47") (pin "1") (pinfunction "1_1") (pintype "passive"))
      (node (ref "T21") (pin "B") (pinfunction "B_B") (pintype "passive"))
    )
    (net (code "121") (name "Net-(R51-Pad1)") (class "Default")
      (node (ref "R51") (pin "1") (pinfunction "1_1") (pintype "passive"))
      (node (ref "T24") (pin "B") (pinfunction "B_B") (pintype "passive"))
    )
    (net (code "122") (name "Net-(R55-Pad1)") (class "Default")
      (node (ref "R55") (pin "1") (pinfunction "1_1") (pintype "passive"))
      (node (ref "T27") (pin "B") (pinfunction "B_B") (pintype "passive"))
    )
    (net (code "123") (name "Net-(R59-Pad1)") (class "Default")
      (node (ref "R59") (pin "1") (pinfunction "1_1") (pintype "passive"))
      (node (ref "T30") (pin "B") (pinfunction "B_B") (pintype "passive"))
    )
    (net (code "124") (name "Net-(R63-Pad1)") (class "Default")
      (node (ref "R63") (pin "1") (pinfunction "1_1") (pintype "passive"))
      (node (ref "T33") (pin "B") (pinfunction "B_B") (pintype "passive"))
    )
    (net (code "125") (name "Net-(R76-Pad1)") (class "Default")
      (node (ref "R76") (pin "1") (pinfunction "1_1") (pintype "passive"))
      (node (ref "T45") (pin "C") (pinfunction "C_C") (pintype "passive"))
    )
    (net (code "126") (name "Net-(R76-Pad2)") (class "Default")
      (node (ref "R76") (pin "2") (pinfunction "2_2") (pintype "passive"))
      (node (ref "T39") (pin "B") (pinfunction "B_B") (pintype "passive"))
    )
    (net (code "127") (name "Net-(R77-Pad1)") (class "Default")
      (node (ref "R77") (pin "1") (pinfunction "1_1") (pintype "passive"))
      (node (ref "T46") (pin "C") (pinfunction "C_C") (pintype "passive"))
    )
    (net (code "128") (name "Net-(R77-Pad2)") (class "Default")
      (node (ref "R77") (pin "2") (pinfunction "2_2") (pintype "passive"))
      (node (ref "T40") (pin "B") (pinfunction "B_B") (pintype "passive"))
    )
    (net (code "129") (name "Net-(R78-Pad1)") (class "Default")
      (node (ref "R78") (pin "1") (pinfunction "1_1") (pintype "passive"))
      (node (ref "T47") (pin "C") (pinfunction "C_C") (pintype "passive"))
    )
    (net (code "130") (name "Net-(R78-Pad2)") (class "Default")
      (node (ref "R78") (pin "2") (pinfunction "2_2") (pintype "passive"))
      (node (ref "T41") (pin "B") (pinfunction "B_B") (pintype "passive"))
    )
    (net (code "131") (name "Net-(R79-Pad1)") (class "Default")
      (node (ref "R79") (pin "1") (pinfunction "1_1") (pintype "passive"))
      (node (ref "T48") (pin "C") (pinfunction "C_C") (pintype "passive"))
    )
    (net (code "132") (name "Net-(R79-Pad2)") (class "Default")
      (node (ref "R79") (pin "2") (pinfunction "2_2") (pintype "passive"))
      (node (ref "T42") (pin "B") (pinfunction "B_B") (pintype "passive"))
    )
    (net (code "133") (name "Net-(R80-Pad1)") (class "Default")
      (node (ref "R80") (pin "1") (pinfunction "1_1") (pintype "passive"))
      (node (ref "T49") (pin "C") (pinfunction "C_C") (pintype "passive"))
    )
    (net (code "134") (name "Net-(R80-Pad2)") (class "Default")
      (node (ref "R80") (pin "2") (pinfunction "2_2") (pintype "passive"))
      (node (ref "T43") (pin "B") (pinfunction "B_B") (pintype "passive"))
    )
    (net (code "135") (name "Net-(R81-Pad1)") (class "Default")
      (node (ref "R81") (pin "1") (pinfunction "1_1") (pintype "passive"))
      (node (ref "T50") (pin "C") (pinfunction "C_C") (pintype "passive"))
    )
    (net (code "136") (name "Net-(R81-Pad2)") (class "Default")
      (node (ref "R81") (pin "2") (pinfunction "2_2") (pintype "passive"))
      (node (ref "T44") (pin "B") (pinfunction "B_B") (pintype "passive"))
    )
    (net (code "137") (name "Net-(R82-Pad2)") (class "Default")
      (node (ref "R82") (pin "2") (pinfunction "2_2") (pintype "passive"))
      (node (ref "T45") (pin "B") (pinfunction "B_B") (pintype "passive"))
    )
    (net (code "138") (name "Net-(R83-Pad2)") (class "Default")
      (node (ref "R83") (pin "2") (pinfunction "2_2") (pintype "passive"))
      (node (ref "T46") (pin "B") (pinfunction "B_B") (pintype "passive"))
    )
    (net (code "139") (name "Net-(R84-Pad2)") (class "Default")
      (node (ref "R84") (pin "2") (pinfunction "2_2") (pintype "passive"))
      (node (ref "T47") (pin "B") (pinfunction "B_B") (pintype "passive"))
    )
    (net (code "140") (name "Net-(R85-Pad2)") (class "Default")
      (node (ref "R85") (pin "2") (pinfunction "2_2") (pintype "passive"))
      (node (ref "T48") (pin "B") (pinfunction "B_B") (pintype "passive"))
    )
    (net (code "141") (name "Net-(R86-Pad2)") (class "Default")
      (node (ref "R86") (pin "2") (pinfunction "2_2") (pintype "passive"))
      (node (ref "T49") (pin "B") (pinfunction "B_B") (pintype "passive"))
    )
    (net (code "142") (name "Net-(R87-Pad2)") (class "Default")
      (node (ref "R87") (pin "2") (pinfunction "2_2") (pintype "passive"))
      (node (ref "T50") (pin "B") (pinfunction "B_B") (pintype "passive"))
    )
    (net (code "143") (name "VCC") (class "Default")
      (node (ref "R100") (pin "1") (pinfunction "1_1") (pintype "passive"))
      (node (ref "R101") (pin "1") (pinfunction "1_1") (pintype "passive"))
      (node (ref "R102") (pin "1") (pinfunction "1_1") (pintype "passive"))
      (node (ref "R103") (pin "1") (pinfunction "1_1") (pintype "passive"))
      (node (ref "R104") (pin "1") (pinfunction "1_1") (pintype "passive"))
      (node (ref "R105") (pin "1") (pinfunction "1_1") (pintype "passive"))
      (node (ref "R106") (pin "1") (pinfunction "1_1") (pintype "passive"))
      (node (ref "R107") (pin "1") (pinfunction "1_1") (pintype "passive"))
      (node (ref "R108") (pin "1") (pinfunction "1_1") (pintype "passive"))
      (node (ref "R109") (pin "1") (pinfunction "1_1") (pintype "passive"))
      (node (ref "R110") (pin "1") (pinfunction "1_1") (pintype "passive"))
      (node (ref "R111") (pin "1") (pinfunction "1_1") (pintype "passive"))
      (node (ref "R41") (pin "1") (pinfunction "1_1") (pintype "passive"))
      (node (ref "R42") (pin "1") (pinfunction "1_1") (pintype "passive"))
      (node (ref "R44") (pin "1") (pinfunction "1_1") (pintype "passive"))
      (node (ref "R45") (pin "1") (pinfunction "1_1") (pintype "passive"))
      (node (ref "R46") (pin "1") (pinfunction "1_1") (pintype "passive"))
      (node (ref "R48") (pin "1") (pinfunction "1_1") (pintype "passive"))
      (node (ref "R49") (pin "1") (pinfunction "1_1") (pintype "passive"))
      (node (ref "R5") (pin "2") (pinfunction "2_2") (pintype "passive"))
      (node (ref "R50") (pin "1") (pinfunction "1_1") (pintype "passive"))
      (node (ref "R52") (pin "1") (pinfunction "1_1") (pintype "passive"))
      (node (ref "R53") (pin "1") (pinfunction "1_1") (pintype "passive"))
      (node (ref "R54") (pin "1") (pinfunction "1_1") (pintype "passive"))
      (node (ref "R56") (pin "1") (pinfunction "1_1") (pintype "passive"))
      (node (ref "R57") (pin "1") (pinfunction "1_1") (pintype "passive"))
      (node (ref "R58") (pin "1") (pinfunction "1_1") (pintype "passive"))
      (node (ref "R6") (pin "2") (pinfunction "2_2") (pintype "passive"))
      (node (ref "R7") (pin "2") (pinfunction "2_2") (pintype "passive"))
      (node (ref "R8") (pin "2") (pinfunction "2_2") (pintype "passive"))
      (node (ref "R88") (pin "1") (pinfunction "1_1") (pintype "passive"))
      (node (ref "R89") (pin "1") (pinfunction "1_1") (pintype "passive"))
      (node (ref "R90") (pin "1") (pinfunction "1_1") (pintype "passive"))
      (node (ref "R91") (pin "1") (pinfunction "1_1") (pintype "passive"))
      (node (ref "R92") (pin "1") (pinfunction "1_1") (pintype "passive"))
      (node (ref "R93") (pin "1") (pinfunction "1_1") (pintype "passive"))
      (node (ref "R94") (pin "1") (pinfunction "1_1") (pintype "passive"))
      (node (ref "R95") (pin "1") (pinfunction "1_1") (pintype "passive"))
      (node (ref "R96") (pin "1") (pinfunction "1_1") (pintype "passive"))
      (node (ref "R97") (pin "1") (pinfunction "1_1") (pintype "passive"))
      (node (ref "R98") (pin "1") (pinfunction "1_1") (pintype "passive"))
      (node (ref "R99") (pin "1") (pinfunction "1_1") (pintype "passive"))
      (node (ref "T39") (pin "E") (pinfunction "E_E") (pintype "passive"))
      (node (ref "T40") (pin "E") (pinfunction "E_E") (pintype "passive"))
      (node (ref "T41") (pin "E") (pinfunction "E_E") (pintype "passive"))
      (node (ref "T42") (pin "E") (pinfunction "E_E") (pintype "passive"))
      (node (ref "T43") (pin "E") (pinfunction "E_E") (pintype "passive"))
      (node (ref "T44") (pin "E") (pinfunction "E_E") (pintype "passive"))
    )
    (net (code "144") (name "unconnected-(DISP1-DP-Pad5)") (class "Default")
      (node (ref "DISP1") (pin "5") (pinfunction "DP_5") (pintype "passive"))
    )
    (net (code "145") (name "unconnected-(R43-Pad2)") (class "Default")
      (node (ref "R43") (pin "2") (pinfunction "2_2") (pintype "passive"))
    )
    (net (code "146") (name "unconnected-(R47-Pad2)") (class "Default")
      (node (ref "R47") (pin "2") (pinfunction "2_2") (pintype "passive"))
    )
    (net (code "147") (name "unconnected-(R51-Pad2)") (class "Default")
      (node (ref "R51") (pin "2") (pinfunction "2_2") (pintype "passive"))
    )
    (net (code "148") (name "unconnected-(R55-Pad2)") (class "Default")
      (node (ref "R55") (pin "2") (pinfunction "2_2") (pintype "passive"))
    )
    (net (code "149") (name "unconnected-(R59-Pad2)") (class "Default")
      (node (ref "R59") (pin "2") (pinfunction "2_2") (pintype "passive"))
    )
    (net (code "150") (name "unconnected-(R63-Pad2)") (class "Default")
      (node (ref "R63") (pin "2") (pinfunction "2_2") (pintype "passive"))
    )
    (net (code "151") (name "unconnected-(T39-PadC)") (class "Default")
      (node (ref "T39") (pin "C") (pinfunction "C_C") (pintype "passive"))
    )
    (net (code "152") (name "unconnected-(T40-PadC)") (class "Default")
      (node (ref "T40") (pin "C") (pinfunction "C_C") (pintype "passive"))
    )
    (net (code "153") (name "unconnected-(T41-PadC)") (class "Default")
      (node (ref "T41") (pin "C") (pinfunction "C_C") (pintype "passive"))
    )
    (net (code "154") (name "unconnected-(T42-PadC)") (class "Default")
      (node (ref "T42") (pin "C") (pinfunction "C_C") (pintype "passive"))
    )
    (net (code "155") (name "unconnected-(T43-PadC)") (class "Default")
      (node (ref "T43") (pin "C") (pinfunction "C_C") (pintype "passive"))
    )
  )
)
